# x9303.net
KiCad netlist of a schematic drawn in EAGLE
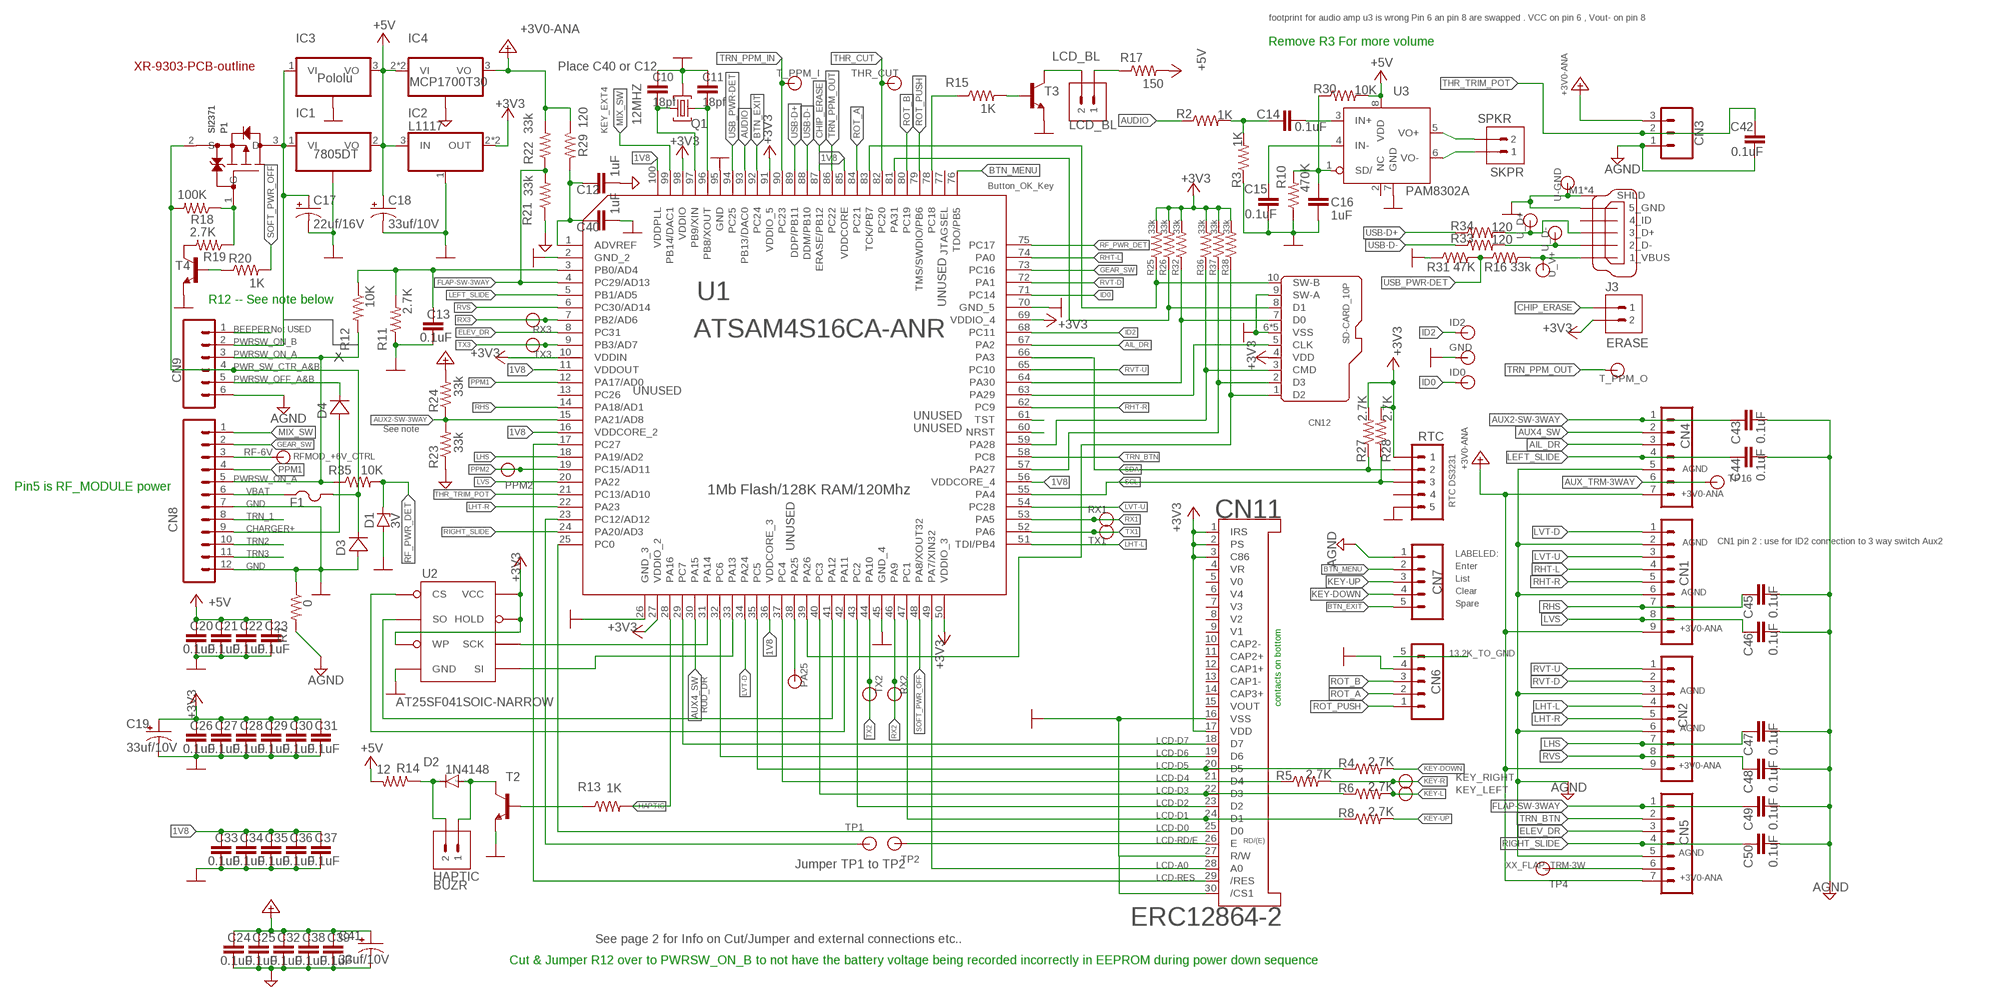
[diagram p0: schematic, sheet 1]
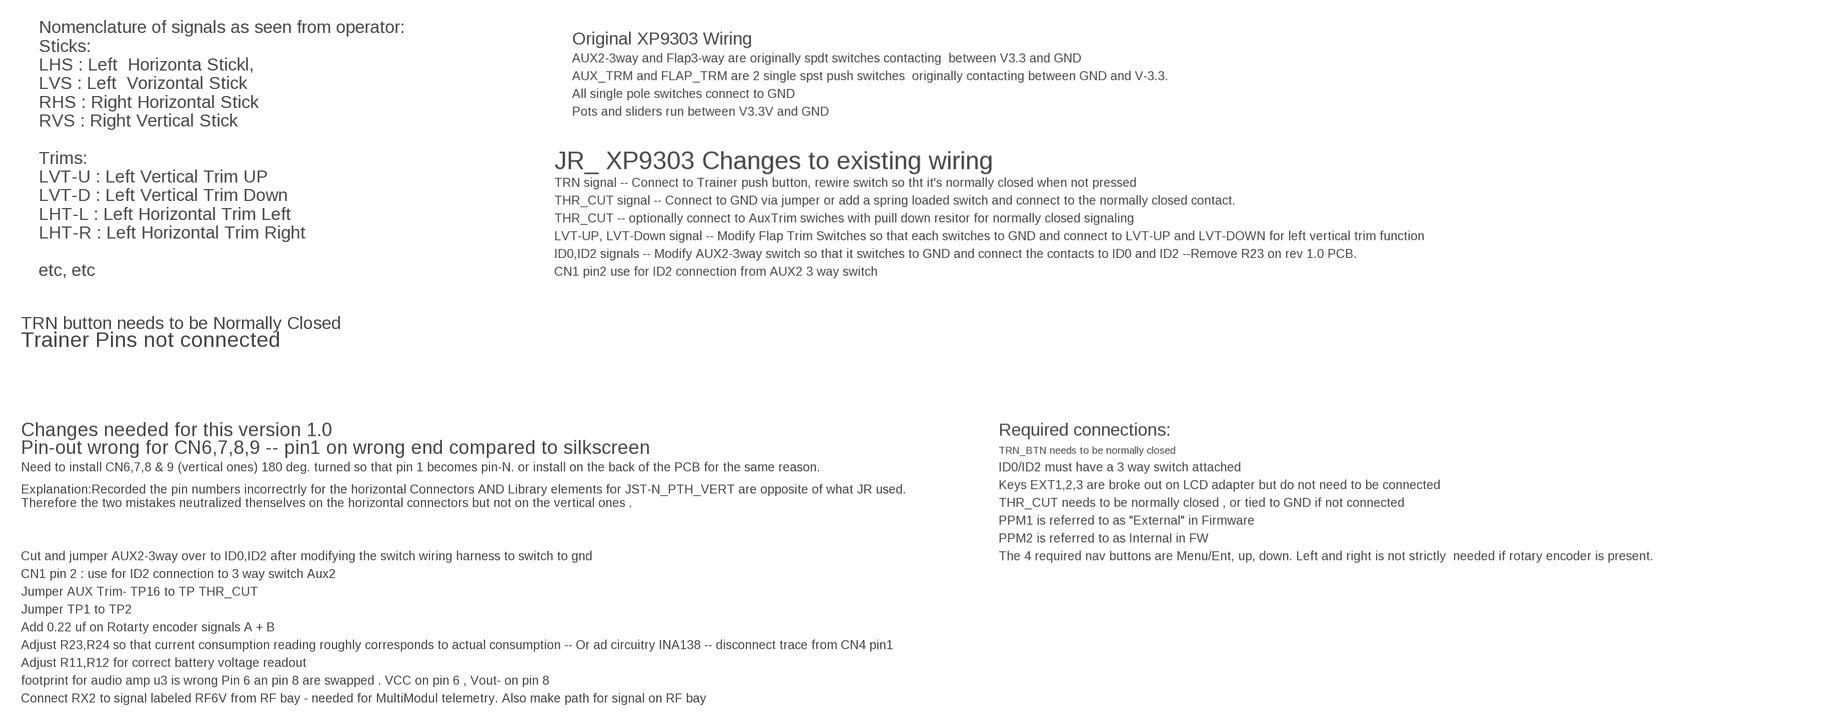
[diagram p1: schematic, sheet 2]
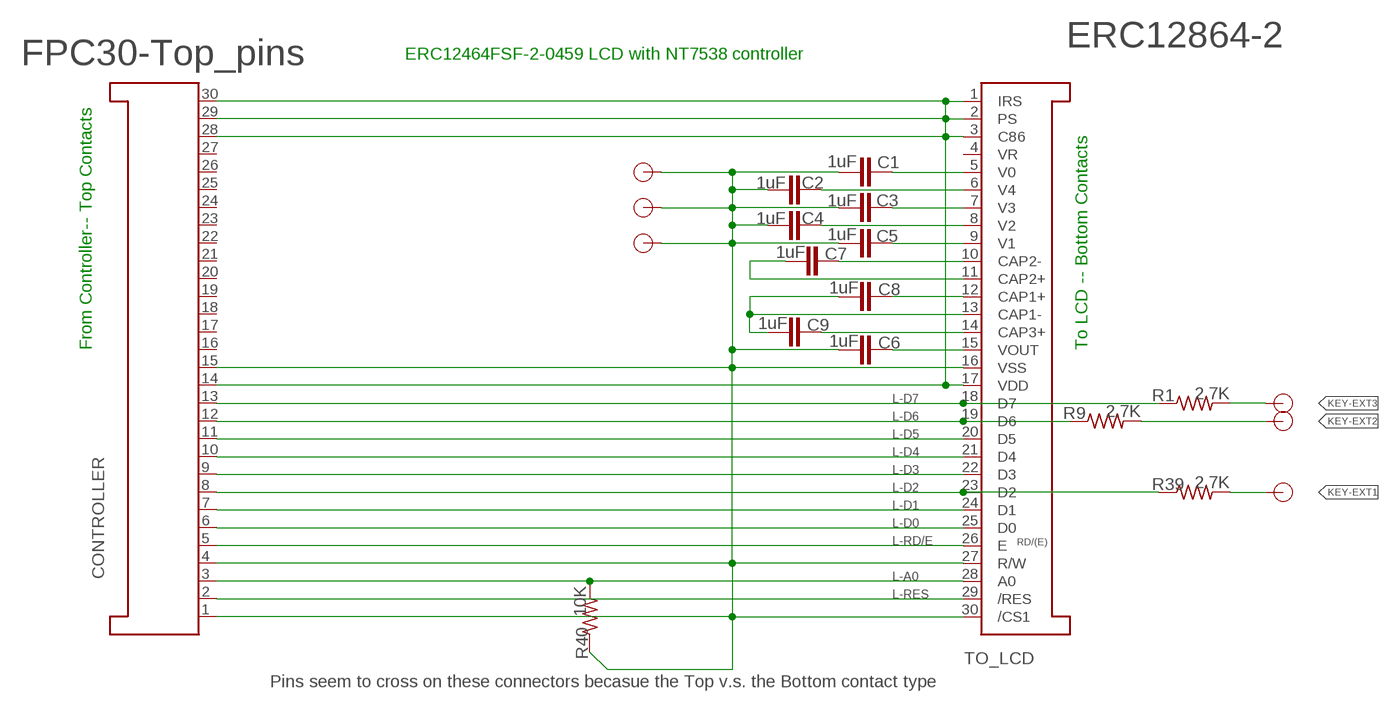
[diagram p2: schematic, sheet 3]

(export (version "E")
  (design (tool "Eeschema 10.0.6"))
  (components
    (comp (ref "BUZR")
      (value "HAPTIC")
      (footprint "eagle-import:1X02")
      (libsource (lib "eagle-import") (part "M02"))
    )
    (comp (ref "C10")
      (value "18pf")
      (footprint "eagle-import:C0603K")
      (libsource (lib "eagle-import") (part "C-EUC0603K"))
    )
    (comp (ref "C11")
      (value "18pf")
      (footprint "eagle-import:C0603K")
      (libsource (lib "eagle-import") (part "C-EUC0603K"))
    )
    (comp (ref "C12")
      (value "1uF")
      (footprint "eagle-import:C0603K")
      (libsource (lib "eagle-import") (part "C-EUC0603K"))
    )
    (comp (ref "C13")
      (value "0.1uF")
      (footprint "eagle-import:C0603K")
      (libsource (lib "eagle-import") (part "C-EUC0603K"))
    )
    (comp (ref "C14")
      (value "0.1uF")
      (footprint "eagle-import:C0603K")
      (libsource (lib "eagle-import") (part "C-EUC0603K"))
    )
    (comp (ref "C15")
      (value "0.1uF")
      (footprint "eagle-import:C0603K")
      (libsource (lib "eagle-import") (part "C-EUC0603K"))
    )
    (comp (ref "C16")
      (value "1uF")
      (footprint "eagle-import:C0603K")
      (libsource (lib "eagle-import") (part "C-EUC0603K"))
    )
    (comp (ref "C17")
      (value "22uf/16V")
      (footprint "eagle-import:SMC_B")
      (libsource (lib "eagle-import") (part "CPOL-USSMCB"))
    )
    (comp (ref "C18")
      (value "33uf/10V")
      (footprint "eagle-import:SMC_B")
      (libsource (lib "eagle-import") (part "CPOL-USSMCB"))
    )
    (comp (ref "C19")
      (value "33uf/10V")
      (footprint "eagle-import:SMC_B")
      (libsource (lib "eagle-import") (part "CPOL-USSMCB"))
    )
    (comp (ref "C20")
      (value "0.1uF")
      (footprint "eagle-import:C0603K")
      (libsource (lib "eagle-import") (part "C-EUC0603K"))
    )
    (comp (ref "C21")
      (value "0.1uF")
      (footprint "eagle-import:C0603K")
      (libsource (lib "eagle-import") (part "C-EUC0603K"))
    )
    (comp (ref "C22")
      (value "0.1uF")
      (footprint "eagle-import:C0603K")
      (libsource (lib "eagle-import") (part "C-EUC0603K"))
    )
    (comp (ref "C23")
      (value "0.1uF")
      (footprint "eagle-import:C0603K")
      (libsource (lib "eagle-import") (part "C-EUC0603K"))
    )
    (comp (ref "C24")
      (value "0.1uF")
      (footprint "eagle-import:C0603K")
      (libsource (lib "eagle-import") (part "C-EUC0603K"))
    )
    (comp (ref "C25")
      (value "0.1uF")
      (footprint "eagle-import:C0603K")
      (libsource (lib "eagle-import") (part "C-EUC0603K"))
    )
    (comp (ref "C26")
      (value "0.1uF")
      (footprint "eagle-import:C0603K")
      (libsource (lib "eagle-import") (part "C-EUC0603K"))
    )
    (comp (ref "C27")
      (value "0.1uF")
      (footprint "eagle-import:C0603K")
      (libsource (lib "eagle-import") (part "C-EUC0603K"))
    )
    (comp (ref "C28")
      (value "0.1uF")
      (footprint "eagle-import:C0603K")
      (libsource (lib "eagle-import") (part "C-EUC0603K"))
    )
    (comp (ref "C29")
      (value "0.1uF")
      (footprint "eagle-import:C0603K")
      (libsource (lib "eagle-import") (part "C-EUC0603K"))
    )
    (comp (ref "C30")
      (value "0.1uF")
      (footprint "eagle-import:C0603K")
      (libsource (lib "eagle-import") (part "C-EUC0603K"))
    )
    (comp (ref "C31")
      (value "0.1uF")
      (footprint "eagle-import:C0603K")
      (libsource (lib "eagle-import") (part "C-EUC0603K"))
    )
    (comp (ref "C32")
      (value "0.1uF")
      (footprint "eagle-import:C0603K")
      (libsource (lib "eagle-import") (part "C-EUC0603K"))
    )
    (comp (ref "C33")
      (value "0.1uF")
      (footprint "eagle-import:C0603K")
      (libsource (lib "eagle-import") (part "C-EUC0603K"))
    )
    (comp (ref "C34")
      (value "0.1uF")
      (footprint "eagle-import:C0603K")
      (libsource (lib "eagle-import") (part "C-EUC0603K"))
    )
    (comp (ref "C35")
      (value "0.1uF")
      (footprint "eagle-import:C0603K")
      (libsource (lib "eagle-import") (part "C-EUC0603K"))
    )
    (comp (ref "C36")
      (value "0.1uF")
      (footprint "eagle-import:C0603K")
      (libsource (lib "eagle-import") (part "C-EUC0603K"))
    )
    (comp (ref "C37")
      (value "0.1uF")
      (footprint "eagle-import:C0603K")
      (libsource (lib "eagle-import") (part "C-EUC0603K"))
    )
    (comp (ref "C38")
      (value "0.1uF")
      (footprint "eagle-import:C0603K")
      (libsource (lib "eagle-import") (part "C-EUC0603K"))
    )
    (comp (ref "C39")
      (value "0.1uF")
      (footprint "eagle-import:C0603K")
      (libsource (lib "eagle-import") (part "C-EUC0603K"))
    )
    (comp (ref "C40")
      (value "1uF")
      (footprint "eagle-import:C0603K")
      (libsource (lib "eagle-import") (part "C-EUC0603K"))
    )
    (comp (ref "C41")
      (value "33uf/10V")
      (footprint "eagle-import:SMC_B")
      (libsource (lib "eagle-import") (part "CPOL-USSMCB"))
    )
    (comp (ref "C42")
      (value "0.1uF")
      (footprint "eagle-import:C0603K")
      (libsource (lib "eagle-import") (part "C-EUC0603K"))
    )
    (comp (ref "C43")
      (value "0.1uF")
      (footprint "eagle-import:C0603K")
      (libsource (lib "eagle-import") (part "C-EUC0603K"))
    )
    (comp (ref "C44")
      (value "0.1uF")
      (footprint "eagle-import:C0603K")
      (libsource (lib "eagle-import") (part "C-EUC0603K"))
    )
    (comp (ref "C45")
      (value "0.1uF")
      (footprint "eagle-import:C0603K")
      (libsource (lib "eagle-import") (part "C-EUC0603K"))
    )
    (comp (ref "C46")
      (value "0.1uF")
      (footprint "eagle-import:C0603K")
      (libsource (lib "eagle-import") (part "C-EUC0603K"))
    )
    (comp (ref "C47")
      (value "0.1uF")
      (footprint "eagle-import:C0603K")
      (libsource (lib "eagle-import") (part "C-EUC0603K"))
    )
    (comp (ref "C48")
      (value "0.1uF")
      (footprint "eagle-import:C0603K")
      (libsource (lib "eagle-import") (part "C-EUC0603K"))
    )
    (comp (ref "C49")
      (value "0.1uF")
      (footprint "eagle-import:C0603K")
      (libsource (lib "eagle-import") (part "C-EUC0603K"))
    )
    (comp (ref "C50")
      (value "0.1uF")
      (footprint "eagle-import:C0603K")
      (libsource (lib "eagle-import") (part "C-EUC0603K"))
    )
    (comp (ref "CN1")
      (value "CONN_09JST-9-PTH-V")
      (footprint "eagle-import:JST-9-PTH-VERT")
      (libsource (lib "eagle-import") (part "CONN_09JST-9-PTH-V"))
    )
    (comp (ref "CN2")
      (value "CONN_09JST-9-PTH-V")
      (footprint "eagle-import:JST-9-PTH-VERT")
      (libsource (lib "eagle-import") (part "CONN_09JST-9-PTH-V"))
    )
    (comp (ref "CN3")
      (value "CONN_03JST-PTH-VERT")
      (footprint "eagle-import:JST-3-PTH-VERT")
      (libsource (lib "eagle-import") (part "CONN_03JST-PTH-VERT"))
    )
    (comp (ref "CN4")
      (value "CONN_07JST-7PTH-V")
      (footprint "eagle-import:JST-7-PTH-VERT")
      (libsource (lib "eagle-import") (part "CONN_07JST-7PTH-V"))
    )
    (comp (ref "CN5")
      (value "CONN_07JST-7PTH-V")
      (footprint "eagle-import:JST-7-PTH-VERT")
      (libsource (lib "eagle-import") (part "CONN_07JST-7PTH-V"))
    )
    (comp (ref "CN6")
      (value "CONN_05JST-VERT")
      (footprint "eagle-import:JST-5-PTH-VERT")
      (libsource (lib "eagle-import") (part "CONN_05JST-VERT"))
    )
    (comp (ref "CN7")
      (value "CONN_05JST-VERT")
      (footprint "eagle-import:JST-5-PTH-VERT")
      (libsource (lib "eagle-import") (part "CONN_05JST-VERT"))
    )
    (comp (ref "CN8")
      (value "CONN_12JST-12-PTH-V")
      (footprint "eagle-import:JST-12-PTH-VERT")
      (libsource (lib "eagle-import") (part "CONN_12JST-12-PTH-V"))
    )
    (comp (ref "CN9")
      (value "CONN_06JST-6-PTH-V")
      (footprint "eagle-import:JST-6-PTH-VERT")
      (libsource (lib "eagle-import") (part "CONN_06JST-6-PTH-V"))
    )
    (comp (ref "CN11")
      (value "ERC12864-2")
      (footprint "eagle-import:FH12-30S-0.5SH")
      (libsource (lib "eagle-import") (part "FPC_30_ERC12864-2"))
    )
    (comp (ref "CN12")
      (value "SD-CARD_10P")
      (footprint "eagle-import:CONN8_DM3D-SF_HIR")
      (libsource (lib "eagle-import") (part "SD-CARD_10P"))
    )
    (comp (ref "D1")
      (value "3V")
      (footprint "eagle-import:SOT23")
      (libsource (lib "eagle-import") (part "ZENER-DIODESOT23"))
    )
    (comp (ref "D2")
      (value "1N4148")
      (footprint "eagle-import:DO35-7")
      (libsource (lib "eagle-import") (part "1N4148DO35-7"))
    )
    (comp (ref "D3")
      (value "MURA220T3G")
      (footprint "eagle-import:SMA")
      (libsource (lib "eagle-import") (part "MURA220T3G"))
    )
    (comp (ref "D4")
      (value "MURA220T3G")
      (footprint "eagle-import:SMA")
      (libsource (lib "eagle-import") (part "MURA220T3G"))
    )
    (comp (ref "F1")
      (value "SMD-FUSE-1206")
      (footprint "eagle-import:R1206")
      (libsource (lib "eagle-import") (part "SMD-FUSE-1206"))
    )
    (comp (ref "GND")
      (value "TP-1")
      (footprint "eagle-import:TP")
      (libsource (lib "eagle-import") (part "TP-1"))
    )
    (comp (ref "IC1")
      (value "7805DT")
      (footprint "eagle-import:TO252")
      (libsource (lib "eagle-import") (part "78DT05"))
    )
    (comp (ref "IC2")
      (value "L1117")
      (footprint "eagle-import:SOT223")
      (fields (field (name "DIGIKEY") "497-17239-1-ND"))
      (libsource (lib "eagle-import") (part "REG1117"))
    )
    (comp (ref "IC3")
      (value "Pololu")
      (footprint "eagle-import:POLOLU")
      (libsource (lib "eagle-import") (part "78"))
    )
    (comp (ref "IC4")
      (value "MCP1700T30")
      (footprint "eagle-import:SOT89")
      (libsource (lib "eagle-import") (part "MCP1700"))
    )
    (comp (ref "ID0")
      (value "TP-1")
      (footprint "eagle-import:TP")
      (libsource (lib "eagle-import") (part "TP-1"))
    )
    (comp (ref "ID2")
      (value "TP-1")
      (footprint "eagle-import:TP")
      (libsource (lib "eagle-import") (part "TP-1"))
    )
    (comp (ref "J3")
      (value "ERASE")
      (footprint "eagle-import:1X02")
      (libsource (lib "eagle-import") (part "M02"))
    )
    (comp (ref "KEY_LEFT")
      (value "TP-1")
      (footprint "eagle-import:TP")
      (libsource (lib "eagle-import") (part "TP-1"))
    )
    (comp (ref "KEY_RIGHT")
      (value "TP-1")
      (footprint "eagle-import:TP")
      (libsource (lib "eagle-import") (part "TP-1"))
    )
    (comp (ref "LCD_BL")
      (value "LCD_BL")
      (footprint "eagle-import:1X02")
      (libsource (lib "eagle-import") (part "M02"))
    )
    (comp (ref "P1")
      (value "SI2371")
      (footprint "eagle-import:SOT23")
      (libsource (lib "eagle-import") (part "SI2371"))
    )
    (comp (ref "PA25")
      (value "TP-1")
      (footprint "eagle-import:TP")
      (libsource (lib "eagle-import") (part "TP-1"))
    )
    (comp (ref "PPM2")
      (value "TP-1")
      (footprint "eagle-import:TP")
      (libsource (lib "eagle-import") (part "TP-1"))
    )
    (comp (ref "Q1")
      (value "12MHZ")
      (footprint "eagle-import:XTAL2.4X2.7")
      (libsource (lib "eagle-import") (part "XTAL_SMD"))
    )
    (comp (ref "R2")
      (value "1K")
      (footprint "eagle-import:R0603")
      (libsource (lib "eagle-import") (part "R-US_R0603"))
    )
    (comp (ref "R3")
      (value "1K")
      (footprint "eagle-import:R0603")
      (libsource (lib "eagle-import") (part "R-US_R0603"))
    )
    (comp (ref "R4")
      (value "2.7K")
      (footprint "eagle-import:R0603")
      (libsource (lib "eagle-import") (part "R-US_R0603"))
    )
    (comp (ref "R5")
      (value "2.7K")
      (footprint "eagle-import:R0603")
      (libsource (lib "eagle-import") (part "R-US_R0603"))
    )
    (comp (ref "R6")
      (value "2.7K")
      (footprint "eagle-import:R0603")
      (libsource (lib "eagle-import") (part "R-US_R0603"))
    )
    (comp (ref "R7")
      (value "0")
      (footprint "eagle-import:R0805")
      (libsource (lib "eagle-import") (part "R-US_R0805"))
    )
    (comp (ref "R8")
      (value "2.7K")
      (footprint "eagle-import:R0603")
      (libsource (lib "eagle-import") (part "R-US_R0603"))
    )
    (comp (ref "R10")
      (value "470K")
      (footprint "eagle-import:R0603")
      (libsource (lib "eagle-import") (part "R-US_R0603"))
    )
    (comp (ref "R11")
      (value "2.7K")
      (footprint "eagle-import:R0603")
      (libsource (lib "eagle-import") (part "R-US_R0603"))
    )
    (comp (ref "R12")
      (value "10K")
      (footprint "eagle-import:R0603")
      (libsource (lib "eagle-import") (part "R-US_R0603"))
    )
    (comp (ref "R13")
      (value "1K")
      (footprint "eagle-import:R0603")
      (libsource (lib "eagle-import") (part "R-US_R0603"))
    )
    (comp (ref "R14")
      (value "12")
      (footprint "eagle-import:R0805")
      (libsource (lib "eagle-import") (part "R-US_R0805"))
    )
    (comp (ref "R15")
      (value "1K")
      (footprint "eagle-import:R0603")
      (libsource (lib "eagle-import") (part "R-US_R0603"))
    )
    (comp (ref "R16")
      (value "33k")
      (footprint "eagle-import:R0603")
      (libsource (lib "eagle-import") (part "R-US_R0603"))
    )
    (comp (ref "R17")
      (value "150")
      (footprint "eagle-import:R0805")
      (libsource (lib "eagle-import") (part "R-US_R0805"))
    )
    (comp (ref "R18")
      (value "100K")
      (footprint "eagle-import:R0603")
      (libsource (lib "eagle-import") (part "R-US_R0603"))
    )
    (comp (ref "R19")
      (value "2.7K")
      (footprint "eagle-import:R0603")
      (libsource (lib "eagle-import") (part "R-US_R0603"))
    )
    (comp (ref "R20")
      (value "1K")
      (footprint "eagle-import:R0603")
      (libsource (lib "eagle-import") (part "R-US_R0603"))
    )
    (comp (ref "R21")
      (value "33k")
      (footprint "eagle-import:R0603")
      (libsource (lib "eagle-import") (part "R-US_R0603"))
    )
    (comp (ref "R22")
      (value "33k")
      (footprint "eagle-import:R0603")
      (libsource (lib "eagle-import") (part "R-US_R0603"))
    )
    (comp (ref "R23")
      (value "33k")
      (footprint "eagle-import:R0603")
      (libsource (lib "eagle-import") (part "R-US_R0603"))
    )
    (comp (ref "R24")
      (value "33k")
      (footprint "eagle-import:R0603")
      (libsource (lib "eagle-import") (part "R-US_R0603"))
    )
    (comp (ref "R25")
      (value "33k")
      (footprint "eagle-import:R0603")
      (libsource (lib "eagle-import") (part "R-US_R0603"))
    )
    (comp (ref "R26")
      (value "33k")
      (footprint "eagle-import:R0603")
      (libsource (lib "eagle-import") (part "R-US_R0603"))
    )
    (comp (ref "R27")
      (value "2.7K")
      (footprint "eagle-import:R0603")
      (libsource (lib "eagle-import") (part "R-US_R0603"))
    )
    (comp (ref "R28")
      (value "2.7K")
      (footprint "eagle-import:R0603")
      (libsource (lib "eagle-import") (part "R-US_R0603"))
    )
    (comp (ref "R29")
      (value "120")
      (footprint "eagle-import:R0603")
      (libsource (lib "eagle-import") (part "R-US_R0603"))
    )
    (comp (ref "R30")
      (value "10K")
      (footprint "eagle-import:R0603")
      (libsource (lib "eagle-import") (part "R-US_R0603"))
    )
    (comp (ref "R31")
      (value "47K")
      (footprint "eagle-import:R0603")
      (libsource (lib "eagle-import") (part "R-US_R0603"))
    )
    (comp (ref "R32")
      (value "33k")
      (footprint "eagle-import:R0603")
      (libsource (lib "eagle-import") (part "R-US_R0603"))
    )
    (comp (ref "R33")
      (value "120")
      (footprint "eagle-import:R0603")
      (libsource (lib "eagle-import") (part "R-US_R0603"))
    )
    (comp (ref "R34")
      (value "120")
      (footprint "eagle-import:R0603")
      (libsource (lib "eagle-import") (part "R-US_R0603"))
    )
    (comp (ref "R35")
      (value "10K")
      (footprint "eagle-import:R0603")
      (libsource (lib "eagle-import") (part "R-US_R0603"))
    )
    (comp (ref "R36")
      (value "33k")
      (footprint "eagle-import:R0603")
      (libsource (lib "eagle-import") (part "R-US_R0603"))
    )
    (comp (ref "R37")
      (value "33k")
      (footprint "eagle-import:R0603")
      (libsource (lib "eagle-import") (part "R-US_R0603"))
    )
    (comp (ref "R38")
      (value "33k")
      (footprint "eagle-import:R0603")
      (libsource (lib "eagle-import") (part "R-US_R0603"))
    )
    (comp (ref "RF-6V")
      (value "TP-1")
      (footprint "eagle-import:TP")
      (libsource (lib "eagle-import") (part "TP-1"))
    )
    (comp (ref "RTC")
      (value "M05PTH")
      (footprint "eagle-import:1X05")
      (libsource (lib "eagle-import") (part "M05PTH"))
    )
    (comp (ref "RX1")
      (value "TP-1")
      (footprint "eagle-import:TP")
      (libsource (lib "eagle-import") (part "TP-1"))
    )
    (comp (ref "RX2")
      (value "TP-1")
      (footprint "eagle-import:TP")
      (libsource (lib "eagle-import") (part "TP-1"))
    )
    (comp (ref "RX3")
      (value "TP-1")
      (footprint "eagle-import:TP")
      (libsource (lib "eagle-import") (part "TP-1"))
    )
    (comp (ref "SPKR")
      (value "SKPR")
      (footprint "eagle-import:1X02")
      (libsource (lib "eagle-import") (part "M02"))
    )
    (comp (ref "T2")
      (value "MMBT3904")
      (footprint "eagle-import:SOT23-BEC")
      (libsource (lib "eagle-import") (part "-NPN-SOT23-BECMMBT3904LT1"))
    )
    (comp (ref "T3")
      (value "MMBT3904")
      (footprint "eagle-import:SOT23-BEC")
      (libsource (lib "eagle-import") (part "-NPN-SOT23-BECMMBT3904LT1"))
    )
    (comp (ref "T4")
      (value "MMBT3904")
      (footprint "eagle-import:SOT23-BEC")
      (libsource (lib "eagle-import") (part "-NPN-SOT23-BECMMBT3904LT1"))
    )
    (comp (ref "THR_CUT")
      (value "TP-1")
      (footprint "eagle-import:TP")
      (libsource (lib "eagle-import") (part "TP-1"))
    )
    (comp (ref "TP1")
      (value "TP-1")
      (footprint "eagle-import:TP")
      (libsource (lib "eagle-import") (part "TP-1"))
    )
    (comp (ref "TP2")
      (value "TP-1")
      (footprint "eagle-import:TP")
      (libsource (lib "eagle-import") (part "TP-1"))
    )
    (comp (ref "TP4")
      (value "TP-1")
      (footprint "eagle-import:TP")
      (libsource (lib "eagle-import") (part "TP-1"))
    )
    (comp (ref "TP16")
      (value "TP-1")
      (footprint "eagle-import:TP")
      (libsource (lib "eagle-import") (part "TP-1"))
    )
    (comp (ref "TX1")
      (value "TP-1")
      (footprint "eagle-import:TP")
      (libsource (lib "eagle-import") (part "TP-1"))
    )
    (comp (ref "TX2")
      (value "TP-1")
      (footprint "eagle-import:TP")
      (libsource (lib "eagle-import") (part "TP-1"))
    )
    (comp (ref "TX3")
      (value "TP-1")
      (footprint "eagle-import:TP")
      (libsource (lib "eagle-import") (part "TP-1"))
    )
    (comp (ref "T_PPM_I")
      (value "TP-1")
      (footprint "eagle-import:TP")
      (libsource (lib "eagle-import") (part "TP-1"))
    )
    (comp (ref "T_PPM_O")
      (value "TP-1")
      (footprint "eagle-import:TP")
      (libsource (lib "eagle-import") (part "TP-1"))
    )
    (comp (ref "U$1")
      (value "XR9303-PCB")
      (footprint "eagle-import:XR9303-PCB_OUTLINE")
      (libsource (lib "eagle-import") (part "XR9303-PCB"))
    )
    (comp (ref "U-GND")
      (value "TP-1")
      (footprint "eagle-import:TP")
      (libsource (lib "eagle-import") (part "TP-1"))
    )
    (comp (ref "U1")
      (value "ATSAM4S16CA-ANR")
      (footprint "eagle-import:TQFP100_14X14MC_MCH")
      (libsource (lib "eagle-import") (part "ATSAM4S16CA-ANR"))
    )
    (comp (ref "U2")
      (value "AT25SF041SOIC-NARROW")
      (footprint "eagle-import:SO08")
      (libsource (lib "eagle-import") (part "AT25F041SOIC-NARROW"))
    )
    (comp (ref "U3")
      (value "PAM8302A")
      (footprint "eagle-import:SOIC_2AADCR_DIO")
      (libsource (lib "eagle-import") (part "PAM8302A"))
    )
    (comp (ref "U_D+")
      (value "TP-1")
      (footprint "eagle-import:TP")
      (libsource (lib "eagle-import") (part "TP-1"))
    )
    (comp (ref "U_D-")
      (value "TP-1")
      (footprint "eagle-import:TP")
      (libsource (lib "eagle-import") (part "TP-1"))
    )
    (comp (ref "U_V+")
      (value "TP-1")
      (footprint "eagle-import:TP")
      (libsource (lib "eagle-import") (part "TP-1"))
    )
    (comp (ref "X2")
      (value "MINI-USB-32005-201")
      (footprint "eagle-import:32005-201")
      (libsource (lib "eagle-import") (part "MINI-USB-32005-201"))
    )
    (comp (ref "C1")
      (value "1uF")
      (footprint "eagle-import:C0805")
      (libsource (lib "eagle-import") (part "C-EUC0805"))
    )
    (comp (ref "C2")
      (value "1uF")
      (footprint "eagle-import:C0805")
      (libsource (lib "eagle-import") (part "C-EUC0805"))
    )
    (comp (ref "C3")
      (value "1uF")
      (footprint "eagle-import:C0805")
      (libsource (lib "eagle-import") (part "C-EUC0805"))
    )
    (comp (ref "C4")
      (value "1uF")
      (footprint "eagle-import:C0805")
      (libsource (lib "eagle-import") (part "C-EUC0805"))
    )
    (comp (ref "C5")
      (value "1uF")
      (footprint "eagle-import:C0805")
      (libsource (lib "eagle-import") (part "C-EUC0805"))
    )
    (comp (ref "C6")
      (value "1uF")
      (footprint "eagle-import:C0805")
      (libsource (lib "eagle-import") (part "C-EUC0805"))
    )
    (comp (ref "C7")
      (value "1uF")
      (footprint "eagle-import:C0805")
      (libsource (lib "eagle-import") (part "C-EUC0805"))
    )
    (comp (ref "C8")
      (value "1uF")
      (footprint "eagle-import:C0805")
      (libsource (lib "eagle-import") (part "C-EUC0805"))
    )
    (comp (ref "C9")
      (value "1uF")
      (footprint "eagle-import:C0805")
      (libsource (lib "eagle-import") (part "C-EUC0805"))
    )
    (comp (ref "CONTROLLER")
      (value "FPC30-Top_pins")
      (footprint "eagle-import:FH12-30S-0.5SH")
      (libsource (lib "eagle-import") (part "FPC_30-PINS"))
    )
    (comp (ref "K1")
      (value "TP-1")
      (footprint "eagle-import:TP")
      (libsource (lib "eagle-import") (part "TP-1"))
    )
    (comp (ref "K2")
      (value "TP-1")
      (footprint "eagle-import:TP")
      (libsource (lib "eagle-import") (part "TP-1"))
    )
    (comp (ref "K3")
      (value "TP-1")
      (footprint "eagle-import:TP")
      (libsource (lib "eagle-import") (part "TP-1"))
    )
    (comp (ref "K_EXT4")
      (value "TP-1")
      (footprint "eagle-import:TP")
      (libsource (lib "eagle-import") (part "TP-1"))
    )
    (comp (ref "K_EXT5")
      (value "TP-1")
      (footprint "eagle-import:TP")
      (libsource (lib "eagle-import") (part "TP-1"))
    )
    (comp (ref "K_EXT6")
      (value "TP-1")
      (footprint "eagle-import:TP")
      (libsource (lib "eagle-import") (part "TP-1"))
    )
    (comp (ref "R1")
      (value "2.7K")
      (footprint "eagle-import:R0603")
      (libsource (lib "eagle-import") (part "R-US_R0603"))
    )
    (comp (ref "R9")
      (value "2.7K")
      (footprint "eagle-import:R0603")
      (libsource (lib "eagle-import") (part "R-US_R0603"))
    )
    (comp (ref "R39")
      (value "2.7K")
      (footprint "eagle-import:R0603")
      (libsource (lib "eagle-import") (part "R-US_R0603"))
    )
    (comp (ref "R40")
      (value "10K")
      (footprint "eagle-import:R0603")
      (libsource (lib "eagle-import") (part "R-US_R0603"))
    )
    (comp (ref "TO_LCD")
      (value "ERC12864-2")
      (footprint "eagle-import:FH12-30S-0.5SH")
      (libsource (lib "eagle-import") (part "FPC_30_ERC12864-2"))
    )
  )
  (nets
    (net (code "1") (name "+3V0-ANA") (class "Default")
      (node (ref "C24") (pin "2") (pinfunction "2_2") (pintype "passive"))
      (node (ref "C25") (pin "2") (pinfunction "2_2") (pintype "passive"))
      (node (ref "C32") (pin "2") (pinfunction "2_2") (pintype "passive"))
      (node (ref "C38") (pin "2") (pinfunction "2_2") (pintype "passive"))
      (node (ref "C39") (pin "2") (pinfunction "2_2") (pintype "passive"))
      (node (ref "C41") (pin "+") (pinfunction "+_+") (pintype "passive"))
      (node (ref "CN1") (pin "9") (pinfunction "9_9") (pintype "passive"))
      (node (ref "CN2") (pin "9") (pinfunction "9_9") (pintype "passive"))
      (node (ref "CN3") (pin "3") (pinfunction "3_3") (pintype "passive"))
      (node (ref "CN4") (pin "7") (pinfunction "7_7") (pintype "passive"))
      (node (ref "CN5") (pin "7") (pinfunction "7_7") (pintype "passive"))
      (node (ref "IC4") (pin "3") (pinfunction "VO_3") (pintype "passive"))
      (node (ref "R22") (pin "2") (pinfunction "2_2") (pintype "passive"))
      (node (ref "R24") (pin "2") (pinfunction "2_2") (pintype "passive"))
      (node (ref "R29") (pin "1") (pinfunction "1_1") (pintype "passive"))
    )
    (net (code "2") (name "+3V3") (class "Default")
      (node (ref "C19") (pin "+") (pinfunction "+_+") (pintype "passive"))
      (node (ref "C26") (pin "2") (pinfunction "2_2") (pintype "passive"))
      (node (ref "C27") (pin "2") (pinfunction "2_2") (pintype "passive"))
      (node (ref "C28") (pin "2") (pinfunction "2_2") (pintype "passive"))
      (node (ref "C29") (pin "2") (pinfunction "2_2") (pintype "passive"))
      (node (ref "C30") (pin "2") (pinfunction "2_2") (pintype "passive"))
      (node (ref "C31") (pin "2") (pinfunction "2_2") (pintype "passive"))
      (node (ref "CN11") (pin "1") (pinfunction "IRS_1") (pintype "bidirectional"))
      (node (ref "CN11") (pin "17") (pinfunction "VDD_17") (pintype "bidirectional"))
      (node (ref "CN11") (pin "2") (pinfunction "PS_2") (pintype "bidirectional"))
      (node (ref "CN11") (pin "3") (pinfunction "C86_3") (pintype "bidirectional"))
      (node (ref "CN12") (pin "4") (pinfunction "VDD_4") (pintype "bidirectional"))
      (node (ref "IC2") (pin "2") (pinfunction "OUT_2") (pintype "output"))
      (node (ref "IC2") (pin "4") (pinfunction "OUT_4") (pintype "output"))
      (node (ref "J3") (pin "2") (pinfunction "2_2") (pintype "passive"))
      (node (ref "R25") (pin "2") (pinfunction "2_2") (pintype "passive"))
      (node (ref "R26") (pin "2") (pinfunction "2_2") (pintype "passive"))
      (node (ref "R27") (pin "2") (pinfunction "2_2") (pintype "passive"))
      (node (ref "R28") (pin "2") (pinfunction "2_2") (pintype "passive"))
      (node (ref "R32") (pin "2") (pinfunction "2_2") (pintype "passive"))
      (node (ref "R36") (pin "2") (pinfunction "2_2") (pintype "passive"))
      (node (ref "R37") (pin "2") (pinfunction "2_2") (pintype "passive"))
      (node (ref "R38") (pin "2") (pinfunction "2_2") (pintype "passive"))
      (node (ref "RTC") (pin "1") (pinfunction "1_1") (pintype "passive"))
      (node (ref "U1") (pin "10") (pinfunction "VDDIN_10") (pintype "power_in"))
      (node (ref "U1") (pin "27") (pinfunction "VDDIO_2_27") (pintype "power_in"))
      (node (ref "U1") (pin "50") (pinfunction "VDDIO_3_50") (pintype "power_in"))
      (node (ref "U1") (pin "69") (pinfunction "VDDIO_4_69") (pintype "power_in"))
      (node (ref "U1") (pin "91") (pinfunction "VDDIO_5_91") (pintype "power_in"))
      (node (ref "U1") (pin "98") (pinfunction "VDDIO_98") (pintype "power_in"))
      (node (ref "U2") (pin "3") (pinfunction "WP_3") (pintype "bidirectional"))
      (node (ref "U2") (pin "7") (pinfunction "HOLD_7") (pintype "bidirectional"))
      (node (ref "U2") (pin "8") (pinfunction "VCC_8") (pintype "bidirectional"))
    )
    (net (code "3") (name "+5V") (class "Default")
      (node (ref "C18") (pin "+") (pinfunction "+_+") (pintype "passive"))
      (node (ref "C20") (pin "2") (pinfunction "2_2") (pintype "passive"))
      (node (ref "C21") (pin "2") (pinfunction "2_2") (pintype "passive"))
      (node (ref "C22") (pin "2") (pinfunction "2_2") (pintype "passive"))
      (node (ref "C23") (pin "2") (pinfunction "2_2") (pintype "passive"))
      (node (ref "IC1") (pin "2") (pinfunction "VO_2") (pintype "passive"))
      (node (ref "IC2") (pin "3") (pinfunction "IN_3") (pintype "input"))
      (node (ref "IC3") (pin "3") (pinfunction "VO_3") (pintype "passive"))
      (node (ref "IC4") (pin "2") (pinfunction "VI_2") (pintype "input"))
      (node (ref "IC4") (pin "4") (pinfunction "VI_4") (pintype "input"))
      (node (ref "R14") (pin "2") (pinfunction "2_2") (pintype "passive"))
      (node (ref "R17") (pin "2") (pinfunction "2_2") (pintype "passive"))
      (node (ref "R30") (pin "2") (pinfunction "2_2") (pintype "passive"))
      (node (ref "U3") (pin "8") (pinfunction "VDD_8") (pintype "power_in"))
    )
    (net (code "4") (name "1V8") (class "Default")
      (node (ref "C33") (pin "2") (pinfunction "2_2") (pintype "passive"))
      (node (ref "C34") (pin "2") (pinfunction "2_2") (pintype "passive"))
      (node (ref "C35") (pin "2") (pinfunction "2_2") (pintype "passive"))
      (node (ref "C36") (pin "2") (pinfunction "2_2") (pintype "passive"))
      (node (ref "C37") (pin "2") (pinfunction "2_2") (pintype "passive"))
      (node (ref "U1") (pin "100") (pinfunction "VDDPLL_100") (pintype "power_in"))
      (node (ref "U1") (pin "11") (pinfunction "VDDOUT_11") (pintype "output"))
      (node (ref "U1") (pin "16") (pinfunction "VDDCORE_2_16") (pintype "power_in"))
      (node (ref "U1") (pin "36") (pinfunction "VDDCORE_3_36") (pintype "power_in"))
      (node (ref "U1") (pin "56") (pinfunction "VDDCORE_4_56") (pintype "power_in"))
      (node (ref "U1") (pin "85") (pinfunction "VDDCORE_85") (pintype "power_in"))
    )
    (net (code "5") (name "13.2K_TO_GND") (class "Default")
      (node (ref "CN6") (pin "5") (pinfunction "5_5") (pintype "passive"))
    )
    (net (code "6") (name "AGND") (class "Default")
      (node (ref "C12") (pin "2") (pinfunction "2_2") (pintype "passive"))
      (node (ref "C24") (pin "1") (pinfunction "1_1") (pintype "passive"))
      (node (ref "C25") (pin "1") (pinfunction "1_1") (pintype "passive"))
      (node (ref "C32") (pin "1") (pinfunction "1_1") (pintype "passive"))
      (node (ref "C38") (pin "1") (pinfunction "1_1") (pintype "passive"))
      (node (ref "C39") (pin "1") (pinfunction "1_1") (pintype "passive"))
      (node (ref "C41") (pin "-") (pinfunction "-_-") (pintype "passive"))
      (node (ref "C42") (pin "1") (pinfunction "1_1") (pintype "passive"))
      (node (ref "C43") (pin "1") (pinfunction "1_1") (pintype "passive"))
      (node (ref "C44") (pin "1") (pinfunction "1_1") (pintype "passive"))
      (node (ref "C45") (pin "1") (pinfunction "1_1") (pintype "passive"))
      (node (ref "C46") (pin "1") (pinfunction "1_1") (pintype "passive"))
      (node (ref "C47") (pin "1") (pinfunction "1_1") (pintype "passive"))
      (node (ref "C48") (pin "1") (pinfunction "1_1") (pintype "passive"))
      (node (ref "C49") (pin "1") (pinfunction "1_1") (pintype "passive"))
      (node (ref "C50") (pin "1") (pinfunction "1_1") (pintype "passive"))
      (node (ref "CN1") (pin "2") (pinfunction "2_2") (pintype "passive"))
      (node (ref "CN1") (pin "6") (pinfunction "6_6") (pintype "passive"))
      (node (ref "CN2") (pin "3") (pinfunction "3_3") (pintype "passive"))
      (node (ref "CN2") (pin "6") (pinfunction "6_6") (pintype "passive"))
      (node (ref "CN3") (pin "1") (pinfunction "1_1") (pintype "passive"))
      (node (ref "CN4") (pin "5") (pinfunction "5_5") (pintype "passive"))
      (node (ref "CN5") (pin "5") (pinfunction "5_5") (pintype "passive"))
      (node (ref "CN7") (pin "1") (pinfunction "1_1") (pintype "passive"))
      (node (ref "CN9") (pin "6") (pinfunction "6_6") (pintype "passive"))
      (node (ref "IC4") (pin "1") (pinfunction "GND_1") (pintype "passive"))
      (node (ref "R21") (pin "1") (pinfunction "1_1") (pintype "passive"))
      (node (ref "R23") (pin "1") (pinfunction "1_1") (pintype "passive"))
      (node (ref "R7") (pin "2") (pinfunction "2_2") (pintype "passive"))
    )
    (net (code "7") (name "AIL_DR") (class "Default")
      (node (ref "CN4") (pin "3") (pinfunction "3_3") (pintype "passive"))
      (node (ref "U1") (pin "67") (pinfunction "PA2_67") (pintype "bidirectional"))
    )
    (net (code "8") (name "AUDIO") (class "Default")
      (node (ref "R2") (pin "1") (pinfunction "1_1") (pintype "passive"))
      (node (ref "U1") (pin "93") (pinfunction "PB13/DAC0_93") (pintype "bidirectional"))
    )
    (net (code "9") (name "AUX2-SW-3WAY") (class "Default")
      (node (ref "C43") (pin "2") (pinfunction "2_2") (pintype "passive"))
      (node (ref "CN4") (pin "1") (pinfunction "1_1") (pintype "passive"))
      (node (ref "R23") (pin "2") (pinfunction "2_2") (pintype "passive"))
      (node (ref "R24") (pin "1") (pinfunction "1_1") (pintype "passive"))
      (node (ref "U1") (pin "15") (pinfunction "PA21/AD8_15") (pintype "bidirectional"))
    )
    (net (code "10") (name "AUX4_SW") (class "Default")
      (node (ref "CN4") (pin "2") (pinfunction "2_2") (pintype "passive"))
      (node (ref "U1") (pin "30") (pinfunction "PA15_30") (pintype "bidirectional"))
    )
    (net (code "11") (name "AUX_TRM-3WAY") (class "Default")
      (node (ref "CN4") (pin "6") (pinfunction "6_6") (pintype "passive"))
      (node (ref "TP16") (pin "P$1") (pinfunction "P$1_P$1") (pintype "bidirectional"))
    )
    (net (code "12") (name "BEEPER") (class "Default")
      (node (ref "CN9") (pin "1") (pinfunction "1_1") (pintype "passive"))
    )
    (net (code "13") (name "BTN_EXIT") (class "Default")
      (node (ref "CN7") (pin "5") (pinfunction "5_5") (pintype "passive"))
      (node (ref "U1") (pin "92") (pinfunction "PC24_92") (pintype "bidirectional"))
    )
    (net (code "14") (name "BTN_MENU") (class "Default")
      (node (ref "CN7") (pin "2") (pinfunction "2_2") (pintype "passive"))
      (node (ref "U1") (pin "76") (pinfunction "TDO/PB5_76") (pintype "passive"))
    )
    (net (code "15") (name "CHARGER+") (class "Default")
      (node (ref "CN8") (pin "9") (pinfunction "9_9") (pintype "passive"))
      (node (ref "D4") (pin "A") (pinfunction "A_A") (pintype "passive"))
    )
    (net (code "16") (name "CHIP_ERASE") (class "Default")
      (node (ref "J3") (pin "1") (pinfunction "1_1") (pintype "passive"))
      (node (ref "U1") (pin "87") (pinfunction "ERASE/PB12_87") (pintype "passive"))
    )
    (net (code "17") (name "ELEV_DR") (class "Default")
      (node (ref "CN5") (pin "3") (pinfunction "3_3") (pintype "passive"))
      (node (ref "U1") (pin "8") (pinfunction "PC31_8") (pintype "bidirectional"))
    )
    (net (code "18") (name "FLAP-SW-3WAY") (class "Default")
      (node (ref "C49") (pin "2") (pinfunction "2_2") (pintype "passive"))
      (node (ref "CN5") (pin "1") (pinfunction "1_1") (pintype "passive"))
      (node (ref "R21") (pin "2") (pinfunction "2_2") (pintype "passive"))
      (node (ref "R22") (pin "1") (pinfunction "1_1") (pintype "passive"))
      (node (ref "U1") (pin "4") (pinfunction "PC29/AD13_4") (pintype "bidirectional"))
    )
    (net (code "19") (name "GEAR_SW") (class "Default")
      (node (ref "CN8") (pin "2") (pinfunction "2_2") (pintype "passive"))
      (node (ref "U1") (pin "73") (pinfunction "PC16_73") (pintype "bidirectional"))
    )
    (net (code "20") (name "GND") (class "Default")
      (node (ref "C10") (pin "1") (pinfunction "1_1") (pintype "passive"))
      (node (ref "C11") (pin "1") (pinfunction "1_1") (pintype "passive"))
      (node (ref "C13") (pin "1") (pinfunction "1_1") (pintype "passive"))
      (node (ref "C15") (pin "1") (pinfunction "1_1") (pintype "passive"))
      (node (ref "C16") (pin "2") (pinfunction "2_2") (pintype "passive"))
      (node (ref "C17") (pin "-") (pinfunction "-_-") (pintype "passive"))
      (node (ref "C18") (pin "-") (pinfunction "-_-") (pintype "passive"))
      (node (ref "C19") (pin "-") (pinfunction "-_-") (pintype "passive"))
      (node (ref "C20") (pin "1") (pinfunction "1_1") (pintype "passive"))
      (node (ref "C21") (pin "1") (pinfunction "1_1") (pintype "passive"))
      (node (ref "C22") (pin "1") (pinfunction "1_1") (pintype "passive"))
      (node (ref "C23") (pin "1") (pinfunction "1_1") (pintype "passive"))
      (node (ref "C26") (pin "1") (pinfunction "1_1") (pintype "passive"))
      (node (ref "C27") (pin "1") (pinfunction "1_1") (pintype "passive"))
      (node (ref "C28") (pin "1") (pinfunction "1_1") (pintype "passive"))
      (node (ref "C29") (pin "1") (pinfunction "1_1") (pintype "passive"))
      (node (ref "C30") (pin "1") (pinfunction "1_1") (pintype "passive"))
      (node (ref "C31") (pin "1") (pinfunction "1_1") (pintype "passive"))
      (node (ref "C33") (pin "1") (pinfunction "1_1") (pintype "passive"))
      (node (ref "C34") (pin "1") (pinfunction "1_1") (pintype "passive"))
      (node (ref "C35") (pin "1") (pinfunction "1_1") (pintype "passive"))
      (node (ref "C36") (pin "1") (pinfunction "1_1") (pintype "passive"))
      (node (ref "C37") (pin "1") (pinfunction "1_1") (pintype "passive"))
      (node (ref "C40") (pin "2") (pinfunction "2_2") (pintype "passive"))
      (node (ref "CN11") (pin "16") (pinfunction "VSS_16") (pintype "bidirectional"))
      (node (ref "CN11") (pin "27") (pinfunction "R/W_27") (pintype "bidirectional"))
      (node (ref "CN11") (pin "30") (pinfunction "/CS1_30") (pintype "bidirectional"))
      (node (ref "CN12") (pin "6") (pinfunction "VSS_6") (pintype "bidirectional"))
      (node (ref "CN12") (pin "9") (pinfunction "SW-A_9") (pintype "bidirectional"))
      (node (ref "CN12") (pin "GND1") (pinfunction "VSS_GND1") (pintype "bidirectional"))
      (node (ref "CN12") (pin "GND2") (pinfunction "VSS_GND2") (pintype "bidirectional"))
      (node (ref "CN12") (pin "GND3") (pinfunction "VSS_GND3") (pintype "bidirectional"))
      (node (ref "CN12") (pin "GND4") (pinfunction "VSS_GND4") (pintype "bidirectional"))
      (node (ref "CN6") (pin "4") (pinfunction "4_4") (pintype "passive"))
      (node (ref "CN8") (pin "12") (pinfunction "12_12") (pintype "passive"))
      (node (ref "CN8") (pin "7") (pinfunction "7_7") (pintype "passive"))
      (node (ref "D1") (pin "1") (pinfunction "A_1") (pintype "passive"))
      (node (ref "D3") (pin "A") (pinfunction "A_A") (pintype "passive"))
      (node (ref "GND") (pin "P$1") (pinfunction "P$1_P$1") (pintype "bidirectional"))
      (node (ref "IC1") (pin "3") (pinfunction "GND_3") (pintype "passive"))
      (node (ref "IC2") (pin "1") (pinfunction "GND_1") (pintype "power_in"))
      (node (ref "IC3") (pin "2") (pinfunction "GND_2") (pintype "passive"))
      (node (ref "Q1") (pin "P$2") (pinfunction "2_P$2") (pintype "passive"))
      (node (ref "Q1") (pin "P$4") (pinfunction "2_P$4") (pintype "passive"))
      (node (ref "R10") (pin "1") (pinfunction "1_1") (pintype "passive"))
      (node (ref "R11") (pin "1") (pinfunction "1_1") (pintype "passive"))
      (node (ref "R3") (pin "1") (pinfunction "1_1") (pintype "passive"))
      (node (ref "R31") (pin "1") (pinfunction "1_1") (pintype "passive"))
      (node (ref "R7") (pin "1") (pinfunction "1_1") (pintype "passive"))
      (node (ref "RTC") (pin "5") (pinfunction "5_5") (pintype "passive"))
      (node (ref "T2") (pin "E") (pinfunction "E_E") (pintype "passive"))
      (node (ref "T3") (pin "E") (pinfunction "E_E") (pintype "passive"))
      (node (ref "T4") (pin "E") (pinfunction "E_E") (pintype "passive"))
      (node (ref "U-GND") (pin "P$1") (pinfunction "P$1_P$1") (pintype "bidirectional"))
      (node (ref "U1") (pin "2") (pinfunction "GND_2_2") (pintype "passive"))
      (node (ref "U1") (pin "26") (pinfunction "GND_3_26") (pintype "passive"))
      (node (ref "U1") (pin "45") (pinfunction "GND_4_45") (pintype "passive"))
      (node (ref "U1") (pin "70") (pinfunction "GND_5_70") (pintype "passive"))
      (node (ref "U1") (pin "95") (pinfunction "GND_95") (pintype "passive"))
      (node (ref "U2") (pin "4") (pinfunction "GND_4") (pintype "bidirectional"))
      (node (ref "U3") (pin "7") (pinfunction "GND_7") (pintype "bidirectional"))
      (node (ref "X2") (pin "5_USB_GND") (pinfunction "5_GND_5_USB_GND") (pintype "passive"))
      (node (ref "X2") (pin "M1") (pinfunction "SHLD_M1") (pintype "passive"))
      (node (ref "X2") (pin "M2") (pinfunction "SHLD_M2") (pintype "passive"))
      (node (ref "X2") (pin "M3") (pinfunction "SHLD_M3") (pintype "passive"))
      (node (ref "X2") (pin "M4") (pinfunction "SHLD_M4") (pintype "passive"))
    )
    (net (code "21") (name "HAPTIC") (class "Default")
      (node (ref "R13") (pin "2") (pinfunction "2_2") (pintype "passive"))
      (node (ref "U1") (pin "28") (pinfunction "PA16_28") (pintype "bidirectional"))
    )
    (net (code "22") (name "ID0") (class "Default")
      (node (ref "ID0") (pin "P$1") (pinfunction "P$1_P$1") (pintype "bidirectional"))
      (node (ref "U1") (pin "71") (pinfunction "PC14_71") (pintype "bidirectional"))
    )
    (net (code "23") (name "ID2") (class "Default")
      (node (ref "ID2") (pin "P$1") (pinfunction "P$1_P$1") (pintype "bidirectional"))
      (node (ref "U1") (pin "68") (pinfunction "PC11_68") (pintype "bidirectional"))
    )
    (net (code "24") (name "KEY-DOWN") (class "Default")
      (node (ref "CN7") (pin "4") (pinfunction "4_4") (pintype "passive"))
      (node (ref "R4") (pin "2") (pinfunction "2_2") (pintype "passive"))
    )
    (net (code "25") (name "KEY-EXT1") (class "Default")
      (node (ref "K1") (pin "P$1") (pinfunction "P$1_P$1") (pintype "bidirectional"))
      (node (ref "R39") (pin "2") (pinfunction "2_2") (pintype "passive"))
    )
    (net (code "26") (name "KEY-EXT2") (class "Default")
      (node (ref "K2") (pin "P$1") (pinfunction "P$1_P$1") (pintype "bidirectional"))
      (node (ref "R9") (pin "2") (pinfunction "2_2") (pintype "passive"))
    )
    (net (code "27") (name "KEY-EXT3") (class "Default")
      (node (ref "K3") (pin "P$1") (pinfunction "P$1_P$1") (pintype "bidirectional"))
      (node (ref "R1") (pin "2") (pinfunction "2_2") (pintype "passive"))
    )
    (net (code "28") (name "KEY-L") (class "Default")
      (node (ref "KEY_LEFT") (pin "P$1") (pinfunction "P$1_P$1") (pintype "bidirectional"))
      (node (ref "R6") (pin "2") (pinfunction "2_2") (pintype "passive"))
    )
    (net (code "29") (name "KEY-R") (class "Default")
      (node (ref "KEY_RIGHT") (pin "P$1") (pinfunction "P$1_P$1") (pintype "bidirectional"))
      (node (ref "R5") (pin "2") (pinfunction "2_2") (pintype "passive"))
    )
    (net (code "30") (name "KEY-UP") (class "Default")
      (node (ref "CN7") (pin "3") (pinfunction "3_3") (pintype "passive"))
      (node (ref "R8") (pin "2") (pinfunction "2_2") (pintype "passive"))
    )
    (net (code "31") (name "L-A0") (class "Default")
      (node (ref "CONTROLLER") (pin "3") (pinfunction "P$3_3") (pintype "bidirectional"))
      (node (ref "R40") (pin "2") (pinfunction "2_2") (pintype "passive"))
      (node (ref "TO_LCD") (pin "28") (pinfunction "A0_28") (pintype "bidirectional"))
    )
    (net (code "32") (name "L-D0") (class "Default")
      (node (ref "CONTROLLER") (pin "6") (pinfunction "P$6_6") (pintype "bidirectional"))
      (node (ref "TO_LCD") (pin "25") (pinfunction "D0_25") (pintype "bidirectional"))
    )
    (net (code "33") (name "L-D1") (class "Default")
      (node (ref "CONTROLLER") (pin "7") (pinfunction "P$7_7") (pintype "bidirectional"))
      (node (ref "TO_LCD") (pin "24") (pinfunction "D1_24") (pintype "bidirectional"))
    )
    (net (code "34") (name "L-D2") (class "Default")
      (node (ref "CONTROLLER") (pin "8") (pinfunction "P$8_8") (pintype "bidirectional"))
      (node (ref "R39") (pin "1") (pinfunction "1_1") (pintype "passive"))
      (node (ref "TO_LCD") (pin "23") (pinfunction "D2_23") (pintype "bidirectional"))
    )
    (net (code "35") (name "L-D3") (class "Default")
      (node (ref "CONTROLLER") (pin "9") (pinfunction "P$9_9") (pintype "bidirectional"))
      (node (ref "TO_LCD") (pin "22") (pinfunction "D3_22") (pintype "bidirectional"))
    )
    (net (code "36") (name "L-D4") (class "Default")
      (node (ref "CONTROLLER") (pin "10") (pinfunction "P$10_10") (pintype "bidirectional"))
      (node (ref "TO_LCD") (pin "21") (pinfunction "D4_21") (pintype "bidirectional"))
    )
    (net (code "37") (name "L-D5") (class "Default")
      (node (ref "CONTROLLER") (pin "11") (pinfunction "P$11_11") (pintype "bidirectional"))
      (node (ref "TO_LCD") (pin "20") (pinfunction "D5_20") (pintype "bidirectional"))
    )
    (net (code "38") (name "L-D6") (class "Default")
      (node (ref "CONTROLLER") (pin "12") (pinfunction "P$12_12") (pintype "bidirectional"))
      (node (ref "R9") (pin "1") (pinfunction "1_1") (pintype "passive"))
      (node (ref "TO_LCD") (pin "19") (pinfunction "D6_19") (pintype "bidirectional"))
    )
    (net (code "39") (name "L-D7") (class "Default")
      (node (ref "CONTROLLER") (pin "13") (pinfunction "P$13_13") (pintype "bidirectional"))
      (node (ref "R1") (pin "1") (pinfunction "1_1") (pintype "passive"))
      (node (ref "TO_LCD") (pin "18") (pinfunction "D7_18") (pintype "bidirectional"))
    )
    (net (code "40") (name "L-RD{slash}E") (class "Default")
      (node (ref "CONTROLLER") (pin "5") (pinfunction "P$5_5") (pintype "bidirectional"))
      (node (ref "TO_LCD") (pin "26") (pinfunction "E_26") (pintype "bidirectional"))
    )
    (net (code "41") (name "L-RES") (class "Default")
      (node (ref "CONTROLLER") (pin "2") (pinfunction "P$2_2") (pintype "bidirectional"))
      (node (ref "TO_LCD") (pin "29") (pinfunction "/RES_29") (pintype "bidirectional"))
    )
    (net (code "42") (name "LCD-A0") (class "Default")
      (node (ref "CN11") (pin "28") (pinfunction "A0_28") (pintype "bidirectional"))
      (node (ref "U1") (pin "49") (pinfunction "PA7/XIN32_49") (pintype "input"))
    )
    (net (code "43") (name "LCD-D0") (class "Default")
      (node (ref "CN11") (pin "25") (pinfunction "D0_25") (pintype "bidirectional"))
      (node (ref "U1") (pin "25") (pinfunction "PC0_25") (pintype "bidirectional"))
    )
    (net (code "44") (name "LCD-D1") (class "Default")
      (node (ref "CN11") (pin "24") (pinfunction "D1_24") (pintype "bidirectional"))
      (node (ref "R8") (pin "1") (pinfunction "1_1") (pintype "passive"))
      (node (ref "U1") (pin "47") (pinfunction "PC1_47") (pintype "bidirectional"))
    )
    (net (code "45") (name "LCD-D2") (class "Default")
      (node (ref "CN11") (pin "23") (pinfunction "D2_23") (pintype "bidirectional"))
      (node (ref "U1") (pin "43") (pinfunction "PC2_43") (pintype "bidirectional"))
    )
    (net (code "46") (name "LCD-D3") (class "Default")
      (node (ref "CN11") (pin "22") (pinfunction "D3_22") (pintype "bidirectional"))
      (node (ref "R6") (pin "1") (pinfunction "1_1") (pintype "passive"))
      (node (ref "U1") (pin "40") (pinfunction "PC3_40") (pintype "bidirectional"))
    )
    (net (code "47") (name "LCD-D4") (class "Default")
      (node (ref "CN11") (pin "21") (pinfunction "D4_21") (pintype "bidirectional"))
      (node (ref "R5") (pin "1") (pinfunction "1_1") (pintype "passive"))
      (node (ref "U1") (pin "37") (pinfunction "PC4_37") (pintype "bidirectional"))
    )
    (net (code "48") (name "LCD-D5") (class "Default")
      (node (ref "CN11") (pin "20") (pinfunction "D5_20") (pintype "bidirectional"))
      (node (ref "R4") (pin "1") (pinfunction "1_1") (pintype "passive"))
      (node (ref "U1") (pin "35") (pinfunction "PC5_35") (pintype "bidirectional"))
    )
    (net (code "49") (name "LCD-D6") (class "Default")
      (node (ref "CN11") (pin "19") (pinfunction "D6_19") (pintype "bidirectional"))
      (node (ref "U1") (pin "32") (pinfunction "PC6_32") (pintype "bidirectional"))
    )
    (net (code "50") (name "LCD-D7") (class "Default")
      (node (ref "CN11") (pin "18") (pinfunction "D7_18") (pintype "bidirectional"))
      (node (ref "U1") (pin "29") (pinfunction "PC7_29") (pintype "bidirectional"))
    )
    (net (code "51") (name "LCD-RD{slash}E") (class "Default")
      (node (ref "CN11") (pin "26") (pinfunction "E_26") (pintype "bidirectional"))
      (node (ref "TP2") (pin "P$1") (pinfunction "P$1_P$1") (pintype "bidirectional"))
    )
    (net (code "52") (name "LCD-RES") (class "Default")
      (node (ref "CN11") (pin "29") (pinfunction "/RES_29") (pintype "bidirectional"))
      (node (ref "U1") (pin "17") (pinfunction "PC27_17") (pintype "bidirectional"))
    )
    (net (code "53") (name "LEFT_SLIDE") (class "Default")
      (node (ref "C44") (pin "2") (pinfunction "2_2") (pintype "passive"))
      (node (ref "CN4") (pin "4") (pinfunction "4_4") (pintype "passive"))
      (node (ref "U1") (pin "5") (pinfunction "PB1/AD5_5") (pintype "bidirectional"))
    )
    (net (code "54") (name "LHS") (class "Default")
      (node (ref "C47") (pin "2") (pinfunction "2_2") (pintype "passive"))
      (node (ref "CN2") (pin "7") (pinfunction "7_7") (pintype "passive"))
      (node (ref "U1") (pin "18") (pinfunction "PA19/AD2_18") (pintype "bidirectional"))
    )
    (net (code "55") (name "LHT-L") (class "Default")
      (node (ref "CN2") (pin "4") (pinfunction "4_4") (pintype "passive"))
      (node (ref "U1") (pin "51") (pinfunction "TDI/PB4_51") (pintype "passive"))
    )
    (net (code "56") (name "LHT-R") (class "Default")
      (node (ref "CN2") (pin "5") (pinfunction "5_5") (pintype "passive"))
      (node (ref "U1") (pin "22") (pinfunction "PA23_22") (pintype "bidirectional"))
    )
    (net (code "57") (name "LVS") (class "Default")
      (node (ref "C46") (pin "2") (pinfunction "2_2") (pintype "passive"))
      (node (ref "CN1") (pin "8") (pinfunction "8_8") (pintype "passive"))
      (node (ref "U1") (pin "20") (pinfunction "PA22_20") (pintype "bidirectional"))
    )
    (net (code "58") (name "LVT-D") (class "Default")
      (node (ref "CN1") (pin "1") (pinfunction "1_1") (pintype "passive"))
      (node (ref "U1") (pin "34") (pinfunction "PA24_34") (pintype "bidirectional"))
    )
    (net (code "59") (name "LVT-U") (class "Default")
      (node (ref "CN1") (pin "3") (pinfunction "3_3") (pintype "passive"))
      (node (ref "U1") (pin "54") (pinfunction "PC28_54") (pintype "bidirectional"))
    )
    (net (code "60") (name "MIX_SW") (class "Default")
      (node (ref "CN8") (pin "1") (pinfunction "1_1") (pintype "passive"))
      (node (ref "U1") (pin "99") (pinfunction "PB14/DAC1_99") (pintype "bidirectional"))
    )
    (net (code "61") (name "Net-(BUZR-Pad1)") (class "Default")
      (node (ref "BUZR") (pin "1") (pinfunction "1_1") (pintype "passive"))
      (node (ref "D2") (pin "A") (pinfunction "A_A") (pintype "passive"))
      (node (ref "T2") (pin "C") (pinfunction "C_C") (pintype "passive"))
    )
    (net (code "62") (name "Net-(BUZR-Pad2)") (class "Default")
      (node (ref "BUZR") (pin "2") (pinfunction "2_2") (pintype "passive"))
      (node (ref "D2") (pin "C") (pinfunction "C_C") (pintype "passive"))
      (node (ref "R14") (pin "1") (pinfunction "1_1") (pintype "passive"))
    )
    (net (code "63") (name "Net-(C14-Pad1)") (class "Default")
      (node (ref "C14") (pin "1") (pinfunction "1_1") (pintype "passive"))
      (node (ref "R2") (pin "2") (pinfunction "2_2") (pintype "passive"))
      (node (ref "R3") (pin "2") (pinfunction "2_2") (pintype "passive"))
    )
    (net (code "64") (name "Net-(CN12-CLK)") (class "Default")
      (node (ref "CN12") (pin "5") (pinfunction "CLK_5") (pintype "bidirectional"))
      (node (ref "U1") (pin "63") (pinfunction "PA29_63") (pintype "bidirectional"))
    )
    (net (code "65") (name "Net-(CN12-CMD)") (class "Default")
      (node (ref "CN12") (pin "3") (pinfunction "CMD_3") (pintype "bidirectional"))
      (node (ref "R36") (pin "1") (pinfunction "1_1") (pintype "passive"))
      (node (ref "U1") (pin "59") (pinfunction "PA28_59") (pintype "bidirectional"))
    )
    (net (code "66") (name "Net-(CN12-D0)") (class "Default")
      (node (ref "CN12") (pin "7") (pinfunction "D0_7") (pintype "bidirectional"))
      (node (ref "R32") (pin "1") (pinfunction "1_1") (pintype "passive"))
      (node (ref "U1") (pin "64") (pinfunction "PA30_64") (pintype "bidirectional"))
    )
    (net (code "67") (name "Net-(CN12-D1)") (class "Default")
      (node (ref "CN12") (pin "8") (pinfunction "D1_8") (pintype "bidirectional"))
      (node (ref "R26") (pin "1") (pinfunction "1_1") (pintype "passive"))
      (node (ref "U1") (pin "81") (pinfunction "PA31_81") (pintype "bidirectional"))
    )
    (net (code "68") (name "Net-(CN12-D2)") (class "Default")
      (node (ref "CN12") (pin "1") (pinfunction "D2_1") (pintype "bidirectional"))
      (node (ref "R38") (pin "1") (pinfunction "1_1") (pintype "passive"))
      (node (ref "U1") (pin "39") (pinfunction "PA26_39") (pintype "bidirectional"))
    )
    (net (code "69") (name "Net-(CN12-D3)") (class "Default")
      (node (ref "CN12") (pin "2") (pinfunction "D3_2") (pintype "bidirectional"))
      (node (ref "R37") (pin "1") (pinfunction "1_1") (pintype "passive"))
      (node (ref "U1") (pin "57") (pinfunction "PA27_57") (pintype "bidirectional"))
    )
    (net (code "70") (name "Net-(CN12-SW-B)") (class "Default")
      (node (ref "CN12") (pin "10") (pinfunction "SW-B_10") (pintype "bidirectional"))
      (node (ref "R25") (pin "1") (pinfunction "1_1") (pintype "passive"))
      (node (ref "U1") (pin "83") (pinfunction "TCK/PB7_83") (pintype "passive"))
    )
    (net (code "71") (name "Net-(CONTROLLER-P$1)") (class "Default")
      (node (ref "C1") (pin "2") (pinfunction "2_2") (pintype "passive"))
      (node (ref "C2") (pin "2") (pinfunction "2_2") (pintype "passive"))
      (node (ref "C3") (pin "2") (pinfunction "2_2") (pintype "passive"))
      (node (ref "C4") (pin "2") (pinfunction "2_2") (pintype "passive"))
      (node (ref "C5") (pin "2") (pinfunction "2_2") (pintype "passive"))
      (node (ref "C6") (pin "2") (pinfunction "2_2") (pintype "passive"))
      (node (ref "CONTROLLER") (pin "1") (pinfunction "P$1_1") (pintype "bidirectional"))
      (node (ref "CONTROLLER") (pin "15") (pinfunction "P$15_15") (pintype "bidirectional"))
      (node (ref "CONTROLLER") (pin "4") (pinfunction "P$4_4") (pintype "bidirectional"))
      (node (ref "K_EXT4") (pin "P$1") (pinfunction "P$1_P$1") (pintype "bidirectional"))
      (node (ref "K_EXT5") (pin "P$1") (pinfunction "P$1_P$1") (pintype "bidirectional"))
      (node (ref "K_EXT6") (pin "P$1") (pinfunction "P$1_P$1") (pintype "bidirectional"))
      (node (ref "R40") (pin "1") (pinfunction "1_1") (pintype "passive"))
      (node (ref "TO_LCD") (pin "16") (pinfunction "VSS_16") (pintype "bidirectional"))
      (node (ref "TO_LCD") (pin "27") (pinfunction "R/W_27") (pintype "bidirectional"))
      (node (ref "TO_LCD") (pin "30") (pinfunction "/CS1_30") (pintype "bidirectional"))
    )
    (net (code "72") (name "Net-(CONTROLLER-P$14)") (class "Default")
      (node (ref "CONTROLLER") (pin "14") (pinfunction "P$14_14") (pintype "bidirectional"))
      (node (ref "CONTROLLER") (pin "28") (pinfunction "P$28_28") (pintype "bidirectional"))
      (node (ref "CONTROLLER") (pin "29") (pinfunction "P$29_29") (pintype "bidirectional"))
      (node (ref "CONTROLLER") (pin "30") (pinfunction "P$30_30") (pintype "bidirectional"))
      (node (ref "TO_LCD") (pin "1") (pinfunction "IRS_1") (pintype "bidirectional"))
      (node (ref "TO_LCD") (pin "17") (pinfunction "VDD_17") (pintype "bidirectional"))
      (node (ref "TO_LCD") (pin "2") (pinfunction "PS_2") (pintype "bidirectional"))
      (node (ref "TO_LCD") (pin "3") (pinfunction "C86_3") (pintype "bidirectional"))
    )
    (net (code "73") (name "Net-(LCD_BL-Pad1)") (class "Default")
      (node (ref "LCD_BL") (pin "1") (pinfunction "1_1") (pintype "passive"))
      (node (ref "R17") (pin "1") (pinfunction "1_1") (pintype "passive"))
    )
    (net (code "74") (name "Net-(LCD_BL-Pad2)") (class "Default")
      (node (ref "LCD_BL") (pin "2") (pinfunction "2_2") (pintype "passive"))
      (node (ref "T3") (pin "C") (pinfunction "C_C") (pintype "passive"))
    )
    (net (code "75") (name "Net-(P1-G)") (class "Default")
      (node (ref "P1") (pin "1") (pinfunction "G_1") (pintype "passive"))
      (node (ref "R18") (pin "1") (pinfunction "1_1") (pintype "passive"))
      (node (ref "R19") (pin "1") (pinfunction "1_1") (pintype "passive"))
    )
    (net (code "76") (name "Net-(Q1-1)") (class "Default")
      (node (ref "C11") (pin "2") (pinfunction "2_2") (pintype "passive"))
      (node (ref "Q1") (pin "P$1") (pinfunction "1_P$1") (pintype "passive"))
      (node (ref "U1") (pin "96") (pinfunction "PB8/XOUT_96") (pintype "output"))
    )
    (net (code "77") (name "Net-(Q1-3)") (class "Default")
      (node (ref "C10") (pin "2") (pinfunction "2_2") (pintype "passive"))
      (node (ref "Q1") (pin "P$3") (pinfunction "3_P$3") (pintype "passive"))
      (node (ref "U1") (pin "97") (pinfunction "PB9/XIN_97") (pintype "bidirectional"))
    )
    (net (code "78") (name "Net-(R13-Pad1)") (class "Default")
      (node (ref "R13") (pin "1") (pinfunction "1_1") (pintype "passive"))
      (node (ref "T2") (pin "B") (pinfunction "B_B") (pintype "passive"))
    )
    (net (code "79") (name "Net-(R15-Pad2)") (class "Default")
      (node (ref "R15") (pin "2") (pinfunction "2_2") (pintype "passive"))
      (node (ref "T3") (pin "B") (pinfunction "B_B") (pintype "passive"))
    )
    (net (code "80") (name "Net-(R16-Pad2)") (class "Default")
      (node (ref "R16") (pin "2") (pinfunction "2_2") (pintype "passive"))
      (node (ref "U_V+") (pin "P$1") (pinfunction "P$1_P$1") (pintype "bidirectional"))
      (node (ref "X2") (pin "1_VBUS") (pinfunction "1_VBUS_1_VBUS") (pintype "passive"))
    )
    (net (code "81") (name "Net-(R19-Pad2)") (class "Default")
      (node (ref "R19") (pin "2") (pinfunction "2_2") (pintype "passive"))
      (node (ref "T4") (pin "C") (pinfunction "C_C") (pintype "passive"))
    )
    (net (code "82") (name "Net-(R20-Pad1)") (class "Default")
      (node (ref "R20") (pin "1") (pinfunction "1_1") (pintype "passive"))
      (node (ref "T4") (pin "B") (pinfunction "B_B") (pintype "passive"))
    )
    (net (code "83") (name "Net-(R33-Pad2)") (class "Default")
      (node (ref "R33") (pin "2") (pinfunction "2_2") (pintype "passive"))
      (node (ref "U_D-") (pin "P$1") (pinfunction "P$1_P$1") (pintype "bidirectional"))
      (node (ref "X2") (pin "2_D-") (pinfunction "2_D-_2_D-") (pintype "passive"))
    )
    (net (code "84") (name "Net-(R34-Pad2)") (class "Default")
      (node (ref "R34") (pin "2") (pinfunction "2_2") (pintype "passive"))
      (node (ref "U_D+") (pin "P$1") (pinfunction "P$1_P$1") (pintype "bidirectional"))
      (node (ref "X2") (pin "3_D+") (pinfunction "3_D+_3_D+") (pintype "passive"))
    )
    (net (code "85") (name "Net-(TO_LCD-CAP1+)") (class "Default")
      (node (ref "C8") (pin "1") (pinfunction "1_1") (pintype "passive"))
      (node (ref "TO_LCD") (pin "12") (pinfunction "CAP1+_12") (pintype "bidirectional"))
    )
    (net (code "86") (name "Net-(TO_LCD-CAP1-)") (class "Default")
      (node (ref "C8") (pin "2") (pinfunction "2_2") (pintype "passive"))
      (node (ref "C9") (pin "2") (pinfunction "2_2") (pintype "passive"))
      (node (ref "TO_LCD") (pin "13") (pinfunction "CAP1-_13") (pintype "bidirectional"))
    )
    (net (code "87") (name "Net-(TO_LCD-CAP2+)") (class "Default")
      (node (ref "C7") (pin "2") (pinfunction "2_2") (pintype "passive"))
      (node (ref "TO_LCD") (pin "11") (pinfunction "CAP2+_11") (pintype "bidirectional"))
    )
    (net (code "88") (name "Net-(TO_LCD-CAP2-)") (class "Default")
      (node (ref "C7") (pin "1") (pinfunction "1_1") (pintype "passive"))
      (node (ref "TO_LCD") (pin "10") (pinfunction "CAP2-_10") (pintype "bidirectional"))
    )
    (net (code "89") (name "Net-(TO_LCD-CAP3+)") (class "Default")
      (node (ref "C9") (pin "1") (pinfunction "1_1") (pintype "passive"))
      (node (ref "TO_LCD") (pin "14") (pinfunction "CAP3+_14") (pintype "bidirectional"))
    )
    (net (code "90") (name "Net-(TO_LCD-V0)") (class "Default")
      (node (ref "C1") (pin "1") (pinfunction "1_1") (pintype "passive"))
      (node (ref "TO_LCD") (pin "5") (pinfunction "V0_5") (pintype "bidirectional"))
    )
    (net (code "91") (name "Net-(TO_LCD-V1)") (class "Default")
      (node (ref "C5") (pin "1") (pinfunction "1_1") (pintype "passive"))
      (node (ref "TO_LCD") (pin "9") (pinfunction "V1_9") (pintype "bidirectional"))
    )
    (net (code "92") (name "Net-(TO_LCD-V2)") (class "Default")
      (node (ref "C4") (pin "1") (pinfunction "1_1") (pintype "passive"))
      (node (ref "TO_LCD") (pin "8") (pinfunction "V2_8") (pintype "bidirectional"))
    )
    (net (code "93") (name "Net-(TO_LCD-V3)") (class "Default")
      (node (ref "C3") (pin "1") (pinfunction "1_1") (pintype "passive"))
      (node (ref "TO_LCD") (pin "7") (pinfunction "V3_7") (pintype "bidirectional"))
    )
    (net (code "94") (name "Net-(TO_LCD-V4)") (class "Default")
      (node (ref "C2") (pin "1") (pinfunction "1_1") (pintype "passive"))
      (node (ref "TO_LCD") (pin "6") (pinfunction "V4_6") (pintype "bidirectional"))
    )
    (net (code "95") (name "Net-(TO_LCD-VOUT)") (class "Default")
      (node (ref "C6") (pin "1") (pinfunction "1_1") (pintype "passive"))
      (node (ref "TO_LCD") (pin "15") (pinfunction "VOUT_15") (pintype "bidirectional"))
    )
    (net (code "96") (name "Net-(U1-ADVREF)") (class "Default")
      (node (ref "C12") (pin "1") (pinfunction "1_1") (pintype "passive"))
      (node (ref "C40") (pin "1") (pinfunction "1_1") (pintype "passive"))
      (node (ref "R29") (pin "2") (pinfunction "2_2") (pintype "passive"))
      (node (ref "U1") (pin "1") (pinfunction "ADVREF_1") (pintype "power_in"))
    )
    (net (code "97") (name "Net-(U1-PA11)") (class "Default")
      (node (ref "U1") (pin "42") (pinfunction "PA11_42") (pintype "bidirectional"))
      (node (ref "U2") (pin "1") (pinfunction "CS_1") (pintype "bidirectional"))
    )
    (net (code "98") (name "Net-(U1-PA12)") (class "Default")
      (node (ref "U1") (pin "41") (pinfunction "PA12_41") (pintype "bidirectional"))
      (node (ref "U2") (pin "2") (pinfunction "SO_2") (pintype "bidirectional"))
    )
    (net (code "99") (name "Net-(U1-PA13)") (class "Default")
      (node (ref "U1") (pin "33") (pinfunction "PA13_33") (pintype "bidirectional"))
      (node (ref "U2") (pin "5") (pinfunction "SI_5") (pintype "bidirectional"))
    )
    (net (code "100") (name "Net-(U1-PA14)") (class "Default")
      (node (ref "U1") (pin "31") (pinfunction "PA14_31") (pintype "bidirectional"))
      (node (ref "U2") (pin "6") (pinfunction "SCK_6") (pintype "bidirectional"))
    )
    (net (code "101") (name "Net-(U1-PA25)") (class "Default")
      (node (ref "PA25") (pin "P$1") (pinfunction "P$1_P$1") (pintype "bidirectional"))
      (node (ref "U1") (pin "38") (pinfunction "PA25_38") (pintype "bidirectional"))
    )
    (net (code "102") (name "Net-(U1-PB0{slash}AD4)") (class "Default")
      (node (ref "C13") (pin "2") (pinfunction "2_2") (pintype "passive"))
      (node (ref "R11") (pin "2") (pinfunction "2_2") (pintype "passive"))
      (node (ref "R12") (pin "1") (pinfunction "1_1") (pintype "passive"))
      (node (ref "U1") (pin "3") (pinfunction "PB0/AD4_3") (pintype "bidirectional"))
    )
    (net (code "103") (name "Net-(U1-PC12{slash}AD12)") (class "Default")
      (node (ref "TP1") (pin "P$1") (pinfunction "P$1_P$1") (pintype "bidirectional"))
      (node (ref "U1") (pin "23") (pinfunction "PC12/AD12_23") (pintype "bidirectional"))
    )
    (net (code "104") (name "Net-(U1-PC18)") (class "Default")
      (node (ref "R15") (pin "1") (pinfunction "1_1") (pintype "passive"))
      (node (ref "U1") (pin "78") (pinfunction "PC18_78") (pintype "bidirectional"))
    )
    (net (code "105") (name "Net-(U3-IN+)") (class "Default")
      (node (ref "C14") (pin "2") (pinfunction "2_2") (pintype "passive"))
      (node (ref "U3") (pin "3") (pinfunction "IN+_3") (pintype "bidirectional"))
    )
    (net (code "106") (name "Net-(U3-IN-)") (class "Default")
      (node (ref "C15") (pin "2") (pinfunction "2_2") (pintype "passive"))
      (node (ref "U3") (pin "4") (pinfunction "IN-_4") (pintype "bidirectional"))
    )
    (net (code "107") (name "Net-(U3-SD{slash})") (class "Default")
      (node (ref "C16") (pin "1") (pinfunction "1_1") (pintype "passive"))
      (node (ref "R10") (pin "2") (pinfunction "2_2") (pintype "passive"))
      (node (ref "R30") (pin "1") (pinfunction "1_1") (pintype "passive"))
      (node (ref "U3") (pin "1") (pinfunction "SD/_1") (pintype "bidirectional"))
    )
    (net (code "108") (name "Net-(U3-VO+)") (class "Default")
      (node (ref "SPKR") (pin "2") (pinfunction "2_2") (pintype "passive"))
      (node (ref "U3") (pin "5") (pinfunction "VO+_5") (pintype "bidirectional"))
    )
    (net (code "109") (name "Net-(U3-VO-)") (class "Default")
      (node (ref "SPKR") (pin "1") (pinfunction "1_1") (pintype "passive"))
      (node (ref "U3") (pin "6") (pinfunction "VO-_6") (pintype "bidirectional"))
    )
    (net (code "110") (name "PPM1") (class "Default")
      (node (ref "CN8") (pin "4") (pinfunction "4_4") (pintype "passive"))
      (node (ref "U1") (pin "12") (pinfunction "PA17/AD0_12") (pintype "bidirectional"))
    )
    (net (code "111") (name "PPM2") (class "Default")
      (node (ref "PPM2") (pin "P$1") (pinfunction "P$1_P$1") (pintype "bidirectional"))
      (node (ref "U1") (pin "19") (pinfunction "PC15/AD11_19") (pintype "bidirectional"))
    )
    (net (code "112") (name "PWRSW_OFF_A&B") (class "Default")
      (node (ref "CN9") (pin "5") (pinfunction "5_5") (pintype "passive"))
      (node (ref "D4") (pin "C") (pinfunction "C_C") (pintype "passive"))
    )
    (net (code "113") (name "PWRSW_ON_A") (class "Default")
      (node (ref "CN8") (pin "5") (pinfunction "5_5") (pintype "passive"))
      (node (ref "CN9") (pin "3") (pinfunction "3_3") (pintype "passive"))
      (node (ref "R12") (pin "2") (pinfunction "2_2") (pintype "passive"))
      (node (ref "R35") (pin "1") (pinfunction "1_1") (pintype "passive"))
    )
    (net (code "114") (name "PWRSW_ON_B") (class "Default")
      (node (ref "C17") (pin "+") (pinfunction "+_+") (pintype "passive"))
      (node (ref "CN9") (pin "2") (pinfunction "2_2") (pintype "passive"))
      (node (ref "IC1") (pin "1") (pinfunction "VI_1") (pintype "input"))
      (node (ref "IC3") (pin "1") (pinfunction "VI_1") (pintype "input"))
      (node (ref "P1") (pin "3") (pinfunction "D_3") (pintype "passive"))
    )
    (net (code "115") (name "PWR_SW_CTR_A&B") (class "Default")
      (node (ref "CN9") (pin "4") (pinfunction "4_4") (pintype "passive"))
      (node (ref "D3") (pin "C") (pinfunction "C_C") (pintype "passive"))
      (node (ref "F1") (pin "2") (pinfunction "2_2") (pintype "passive"))
      (node (ref "P1") (pin "2") (pinfunction "S_2") (pintype "passive"))
      (node (ref "R18") (pin "2") (pinfunction "2_2") (pintype "passive"))
    )
    (net (code "116") (name "RFMOD_+6V_CTRL") (class "Default")
      (node (ref "CN8") (pin "3") (pinfunction "3_3") (pintype "passive"))
      (node (ref "RF-6V") (pin "P$1") (pinfunction "P$1_P$1") (pintype "bidirectional"))
    )
    (net (code "117") (name "RF_PWR_DET") (class "Default")
      (node (ref "D1") (pin "3") (pinfunction "C_3") (pintype "passive"))
      (node (ref "R35") (pin "2") (pinfunction "2_2") (pintype "passive"))
      (node (ref "U1") (pin "75") (pinfunction "PC17_75") (pintype "bidirectional"))
    )
    (net (code "118") (name "RHS") (class "Default")
      (node (ref "C45") (pin "2") (pinfunction "2_2") (pintype "passive"))
      (node (ref "CN1") (pin "7") (pinfunction "7_7") (pintype "passive"))
      (node (ref "U1") (pin "14") (pinfunction "PA18/AD1_14") (pintype "bidirectional"))
    )
    (net (code "119") (name "RHT-L") (class "Default")
      (node (ref "CN1") (pin "4") (pinfunction "4_4") (pintype "passive"))
      (node (ref "U1") (pin "74") (pinfunction "PA0_74") (pintype "bidirectional"))
    )
    (net (code "120") (name "RHT-R") (class "Default")
      (node (ref "CN1") (pin "5") (pinfunction "5_5") (pintype "passive"))
      (node (ref "U1") (pin "62") (pinfunction "PC9_62") (pintype "bidirectional"))
    )
    (net (code "121") (name "RIGHT_SLIDE") (class "Default")
      (node (ref "C50") (pin "2") (pinfunction "2_2") (pintype "passive"))
      (node (ref "CN5") (pin "4") (pinfunction "4_4") (pintype "passive"))
      (node (ref "U1") (pin "24") (pinfunction "PA20/AD3_24") (pintype "bidirectional"))
    )
    (net (code "122") (name "ROT_A") (class "Default")
      (node (ref "CN6") (pin "2") (pinfunction "2_2") (pintype "passive"))
      (node (ref "U1") (pin "84") (pinfunction "PC21_84") (pintype "bidirectional"))
    )
    (net (code "123") (name "ROT_B") (class "Default")
      (node (ref "CN6") (pin "3") (pinfunction "3_3") (pintype "passive"))
      (node (ref "U1") (pin "80") (pinfunction "PC19_80") (pintype "bidirectional"))
    )
    (net (code "124") (name "ROT_PUSH") (class "Default")
      (node (ref "CN6") (pin "1") (pinfunction "1_1") (pintype "passive"))
      (node (ref "U1") (pin "79") (pinfunction "TMS/SWDIO/PB6_79") (pintype "passive"))
    )
    (net (code "125") (name "RVS") (class "Default")
      (node (ref "C48") (pin "2") (pinfunction "2_2") (pintype "passive"))
      (node (ref "CN2") (pin "8") (pinfunction "8_8") (pintype "passive"))
      (node (ref "U1") (pin "6") (pinfunction "PC30/AD14_6") (pintype "bidirectional"))
    )
    (net (code "126") (name "RVT-D") (class "Default")
      (node (ref "CN2") (pin "2") (pinfunction "2_2") (pintype "passive"))
      (node (ref "U1") (pin "72") (pinfunction "PA1_72") (pintype "bidirectional"))
    )
    (net (code "127") (name "RVT-U") (class "Default")
      (node (ref "CN2") (pin "1") (pinfunction "1_1") (pintype "passive"))
      (node (ref "U1") (pin "65") (pinfunction "PC10_65") (pintype "bidirectional"))
    )
    (net (code "128") (name "RX1") (class "Default")
      (node (ref "RX1") (pin "P$1") (pinfunction "P$1_P$1") (pintype "bidirectional"))
      (node (ref "U1") (pin "53") (pinfunction "PA5_53") (pintype "bidirectional"))
    )
    (net (code "129") (name "RX2") (class "Default")
      (node (ref "RX2") (pin "P$1") (pinfunction "P$1_P$1") (pintype "bidirectional"))
      (node (ref "U1") (pin "46") (pinfunction "PA9_46") (pintype "bidirectional"))
    )
    (net (code "130") (name "RX3") (class "Default")
      (node (ref "RX3") (pin "P$1") (pinfunction "P$1_P$1") (pintype "bidirectional"))
      (node (ref "U1") (pin "7") (pinfunction "PB2/AD6_7") (pintype "bidirectional"))
    )
    (net (code "131") (name "SCL") (class "Default")
      (node (ref "R28") (pin "1") (pinfunction "1_1") (pintype "passive"))
      (node (ref "RTC") (pin "3") (pinfunction "3_3") (pintype "passive"))
      (node (ref "U1") (pin "55") (pinfunction "PA4_55") (pintype "bidirectional"))
    )
    (net (code "132") (name "SDA") (class "Default")
      (node (ref "R27") (pin "1") (pinfunction "1_1") (pintype "passive"))
      (node (ref "RTC") (pin "2") (pinfunction "2_2") (pintype "passive"))
      (node (ref "U1") (pin "66") (pinfunction "PA3_66") (pintype "bidirectional"))
    )
    (net (code "133") (name "SOFT_PWR_OFF") (class "Default")
      (node (ref "R20") (pin "2") (pinfunction "2_2") (pintype "passive"))
      (node (ref "U1") (pin "48") (pinfunction "PA8/XOUT32_48") (pintype "output"))
    )
    (net (code "134") (name "THR_CUT") (class "Default")
      (node (ref "THR_CUT") (pin "P$1") (pinfunction "P$1_P$1") (pintype "bidirectional"))
      (node (ref "U1") (pin "82") (pinfunction "PC20_82") (pintype "bidirectional"))
    )
    (net (code "135") (name "THR_TRIM_POT") (class "Default")
      (node (ref "C42") (pin "2") (pinfunction "2_2") (pintype "passive"))
      (node (ref "CN3") (pin "2") (pinfunction "2_2") (pintype "passive"))
      (node (ref "U1") (pin "21") (pinfunction "PC13/AD10_21") (pintype "bidirectional"))
    )
    (net (code "136") (name "TRN2") (class "Default")
      (node (ref "CN8") (pin "10") (pinfunction "10_10") (pintype "passive"))
    )
    (net (code "137") (name "TRN3") (class "Default")
      (node (ref "CN8") (pin "11") (pinfunction "11_11") (pintype "passive"))
    )
    (net (code "138") (name "TRN_1") (class "Default")
      (node (ref "CN8") (pin "8") (pinfunction "8_8") (pintype "passive"))
    )
    (net (code "139") (name "TRN_BTN") (class "Default")
      (node (ref "CN5") (pin "2") (pinfunction "2_2") (pintype "passive"))
      (node (ref "U1") (pin "58") (pinfunction "PC8_58") (pintype "bidirectional"))
    )
    (net (code "140") (name "TRN_PPM_IN") (class "Default")
      (node (ref "T_PPM_I") (pin "P$1") (pinfunction "P$1_P$1") (pintype "bidirectional"))
      (node (ref "U1") (pin "90") (pinfunction "PC23_90") (pintype "bidirectional"))
    )
    (net (code "141") (name "TRN_PPM_OUT") (class "Default")
      (node (ref "T_PPM_O") (pin "P$1") (pinfunction "P$1_P$1") (pintype "bidirectional"))
      (node (ref "U1") (pin "86") (pinfunction "PC22_86") (pintype "bidirectional"))
    )
    (net (code "142") (name "TX1") (class "Default")
      (node (ref "TX1") (pin "P$1") (pinfunction "P$1_P$1") (pintype "bidirectional"))
      (node (ref "U1") (pin "52") (pinfunction "PA6_52") (pintype "bidirectional"))
    )
    (net (code "143") (name "TX2") (class "Default")
      (node (ref "TX2") (pin "P$1") (pinfunction "P$1_P$1") (pintype "bidirectional"))
      (node (ref "U1") (pin "44") (pinfunction "PA10_44") (pintype "bidirectional"))
    )
    (net (code "144") (name "TX3") (class "Default")
      (node (ref "TX3") (pin "P$1") (pinfunction "P$1_P$1") (pintype "bidirectional"))
      (node (ref "U1") (pin "9") (pinfunction "PB3/AD7_9") (pintype "bidirectional"))
    )
    (net (code "145") (name "USB-D+") (class "Default")
      (node (ref "R34") (pin "1") (pinfunction "1_1") (pintype "passive"))
      (node (ref "U1") (pin "89") (pinfunction "DDP/PB11_89") (pintype "passive"))
    )
    (net (code "146") (name "USB-D-") (class "Default")
      (node (ref "R33") (pin "1") (pinfunction "1_1") (pintype "passive"))
      (node (ref "U1") (pin "88") (pinfunction "DDM/PB10_88") (pintype "passive"))
    )
    (net (code "147") (name "USB_PWR-DET") (class "Default")
      (node (ref "R16") (pin "1") (pinfunction "1_1") (pintype "passive"))
      (node (ref "R31") (pin "2") (pinfunction "2_2") (pintype "passive"))
      (node (ref "U1") (pin "94") (pinfunction "PC25_94") (pintype "bidirectional"))
    )
    (net (code "148") (name "VBAT") (class "Default")
      (node (ref "CN8") (pin "6") (pinfunction "6_6") (pintype "passive"))
      (node (ref "F1") (pin "1") (pinfunction "1_1") (pintype "passive"))
    )
    (net (code "149") (name "XX_FLAP_TRM-3W") (class "Default")
      (node (ref "CN5") (pin "6") (pinfunction "6_6") (pintype "passive"))
      (node (ref "TP4") (pin "P$1") (pinfunction "P$1_P$1") (pintype "bidirectional"))
    )
    (net (code "150") (name "unconnected-(CN11-CAP1+-Pad12)") (class "Default")
      (node (ref "CN11") (pin "12") (pinfunction "CAP1+_12") (pintype "bidirectional"))
    )
    (net (code "151") (name "unconnected-(CN11-CAP1--Pad13)") (class "Default")
      (node (ref "CN11") (pin "13") (pinfunction "CAP1-_13") (pintype "bidirectional"))
    )
    (net (code "152") (name "unconnected-(CN11-CAP2+-Pad11)") (class "Default")
      (node (ref "CN11") (pin "11") (pinfunction "CAP2+_11") (pintype "bidirectional"))
    )
    (net (code "153") (name "unconnected-(CN11-CAP2--Pad10)") (class "Default")
      (node (ref "CN11") (pin "10") (pinfunction "CAP2-_10") (pintype "bidirectional"))
    )
    (net (code "154") (name "unconnected-(CN11-CAP3+-Pad14)") (class "Default")
      (node (ref "CN11") (pin "14") (pinfunction "CAP3+_14") (pintype "bidirectional"))
    )
    (net (code "155") (name "unconnected-(CN11-V0-Pad5)") (class "Default")
      (node (ref "CN11") (pin "5") (pinfunction "V0_5") (pintype "bidirectional"))
    )
    (net (code "156") (name "unconnected-(CN11-V1-Pad9)") (class "Default")
      (node (ref "CN11") (pin "9") (pinfunction "V1_9") (pintype "bidirectional"))
    )
    (net (code "157") (name "unconnected-(CN11-V2-Pad8)") (class "Default")
      (node (ref "CN11") (pin "8") (pinfunction "V2_8") (pintype "bidirectional"))
    )
    (net (code "158") (name "unconnected-(CN11-V3-Pad7)") (class "Default")
      (node (ref "CN11") (pin "7") (pinfunction "V3_7") (pintype "bidirectional"))
    )
    (net (code "159") (name "unconnected-(CN11-V4-Pad6)") (class "Default")
      (node (ref "CN11") (pin "6") (pinfunction "V4_6") (pintype "bidirectional"))
    )
    (net (code "160") (name "unconnected-(CN11-VOUT-Pad15)") (class "Default")
      (node (ref "CN11") (pin "15") (pinfunction "VOUT_15") (pintype "bidirectional"))
    )
    (net (code "161") (name "unconnected-(CN11-VR-Pad4)") (class "Default")
      (node (ref "CN11") (pin "4") (pinfunction "VR_4") (pintype "bidirectional"))
    )
    (net (code "162") (name "unconnected-(CONTROLLER-P$16-Pad16)") (class "Default")
      (node (ref "CONTROLLER") (pin "16") (pinfunction "P$16_16") (pintype "bidirectional"))
    )
    (net (code "163") (name "unconnected-(CONTROLLER-P$17-Pad17)") (class "Default")
      (node (ref "CONTROLLER") (pin "17") (pinfunction "P$17_17") (pintype "bidirectional"))
    )
    (net (code "164") (name "unconnected-(CONTROLLER-P$18-Pad18)") (class "Default")
      (node (ref "CONTROLLER") (pin "18") (pinfunction "P$18_18") (pintype "bidirectional"))
    )
    (net (code "165") (name "unconnected-(CONTROLLER-P$19-Pad19)") (class "Default")
      (node (ref "CONTROLLER") (pin "19") (pinfunction "P$19_19") (pintype "bidirectional"))
    )
    (net (code "166") (name "unconnected-(CONTROLLER-P$20-Pad20)") (class "Default")
      (node (ref "CONTROLLER") (pin "20") (pinfunction "P$20_20") (pintype "bidirectional"))
    )
    (net (code "167") (name "unconnected-(CONTROLLER-P$21-Pad21)") (class "Default")
      (node (ref "CONTROLLER") (pin "21") (pinfunction "P$21_21") (pintype "bidirectional"))
    )
    (net (code "168") (name "unconnected-(CONTROLLER-P$22-Pad22)") (class "Default")
      (node (ref "CONTROLLER") (pin "22") (pinfunction "P$22_22") (pintype "bidirectional"))
    )
    (net (code "169") (name "unconnected-(CONTROLLER-P$23-Pad23)") (class "Default")
      (node (ref "CONTROLLER") (pin "23") (pinfunction "P$23_23") (pintype "bidirectional"))
    )
    (net (code "170") (name "unconnected-(CONTROLLER-P$24-Pad24)") (class "Default")
      (node (ref "CONTROLLER") (pin "24") (pinfunction "P$24_24") (pintype "bidirectional"))
    )
    (net (code "171") (name "unconnected-(CONTROLLER-P$25-Pad25)") (class "Default")
      (node (ref "CONTROLLER") (pin "25") (pinfunction "P$25_25") (pintype "bidirectional"))
    )
    (net (code "172") (name "unconnected-(CONTROLLER-P$26-Pad26)") (class "Default")
      (node (ref "CONTROLLER") (pin "26") (pinfunction "P$26_26") (pintype "bidirectional"))
    )
    (net (code "173") (name "unconnected-(CONTROLLER-P$27-Pad27)") (class "Default")
      (node (ref "CONTROLLER") (pin "27") (pinfunction "P$27_27") (pintype "bidirectional"))
    )
    (net (code "174") (name "unconnected-(RTC-Pad4)") (class "Default")
      (node (ref "RTC") (pin "4") (pinfunction "4_4") (pintype "passive"))
    )
    (net (code "175") (name "unconnected-(TO_LCD-VR-Pad4)") (class "Default")
      (node (ref "TO_LCD") (pin "4") (pinfunction "VR_4") (pintype "bidirectional"))
    )
    (net (code "176") (name "unconnected-(U1-JTAGSEL-Pad77)") (class "Default")
      (node (ref "U1") (pin "77") (pinfunction "JTAGSEL_77") (pintype "passive"))
    )
    (net (code "177") (name "unconnected-(U1-NRST-Pad60)") (class "Default")
      (node (ref "U1") (pin "60") (pinfunction "NRST_60") (pintype "passive"))
    )
    (net (code "178") (name "unconnected-(U1-PC26-Pad13)") (class "Default")
      (node (ref "U1") (pin "13") (pinfunction "PC26_13") (pintype "bidirectional"))
    )
    (net (code "179") (name "unconnected-(U1-TST-Pad61)") (class "Default")
      (node (ref "U1") (pin "61") (pinfunction "TST_61") (pintype "passive"))
    )
    (net (code "180") (name "unconnected-(U3-NC-Pad2)") (class "Default")
      (node (ref "U3") (pin "2") (pinfunction "NC_2") (pintype "no_connect"))
    )
    (net (code "181") (name "unconnected-(X2-Pad4_ID)") (class "Default")
      (node (ref "X2") (pin "4_ID") (pinfunction "4_ID_4_ID") (pintype "passive"))
    )
  )
)
